# TAMDL_V2.net
KiCad netlist of a schematic drawn in EAGLE
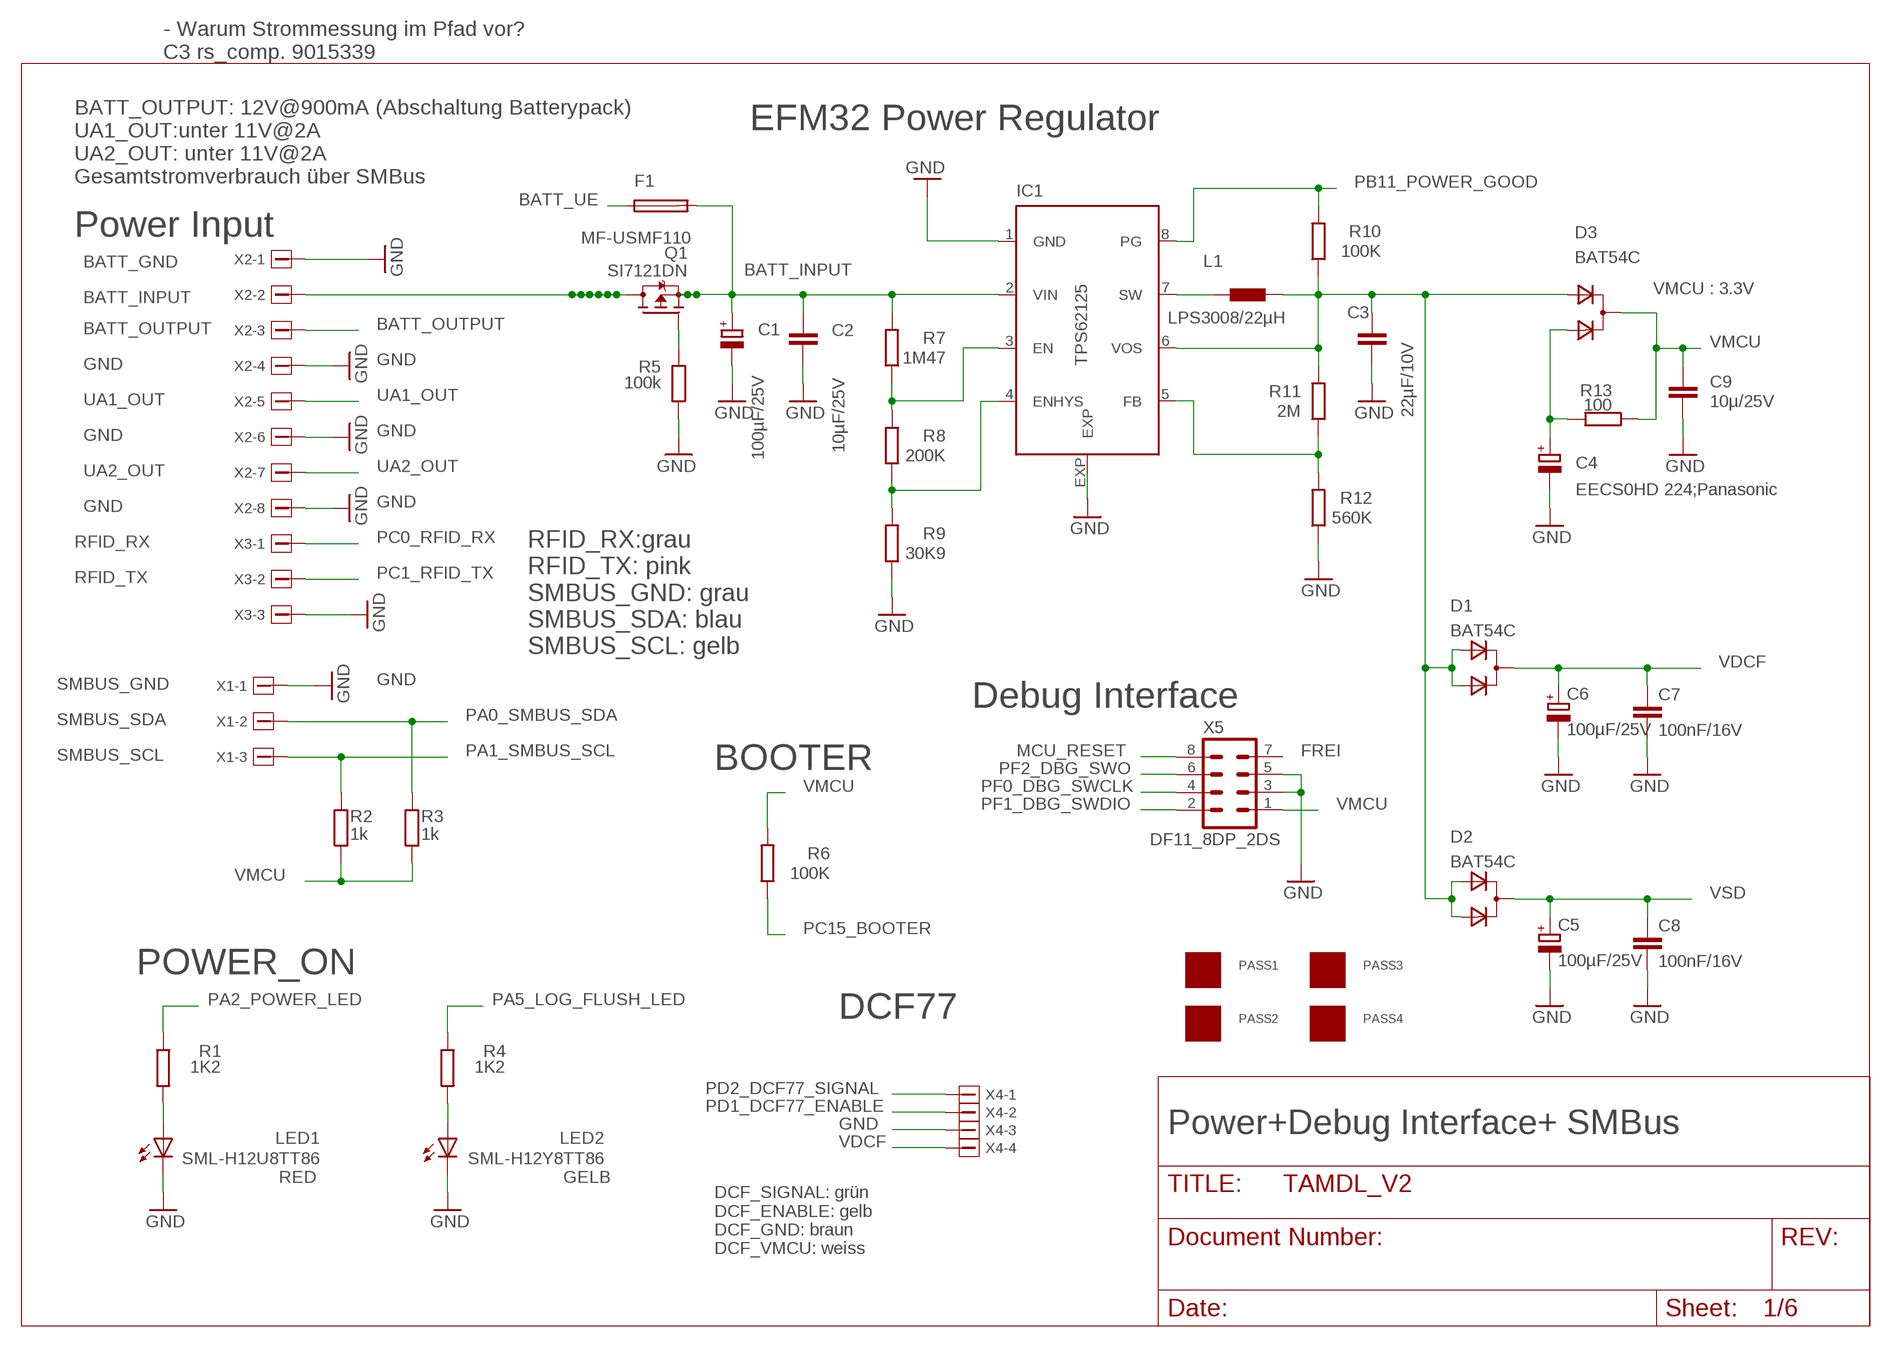
[diagram p0: schematic, sheet 1]
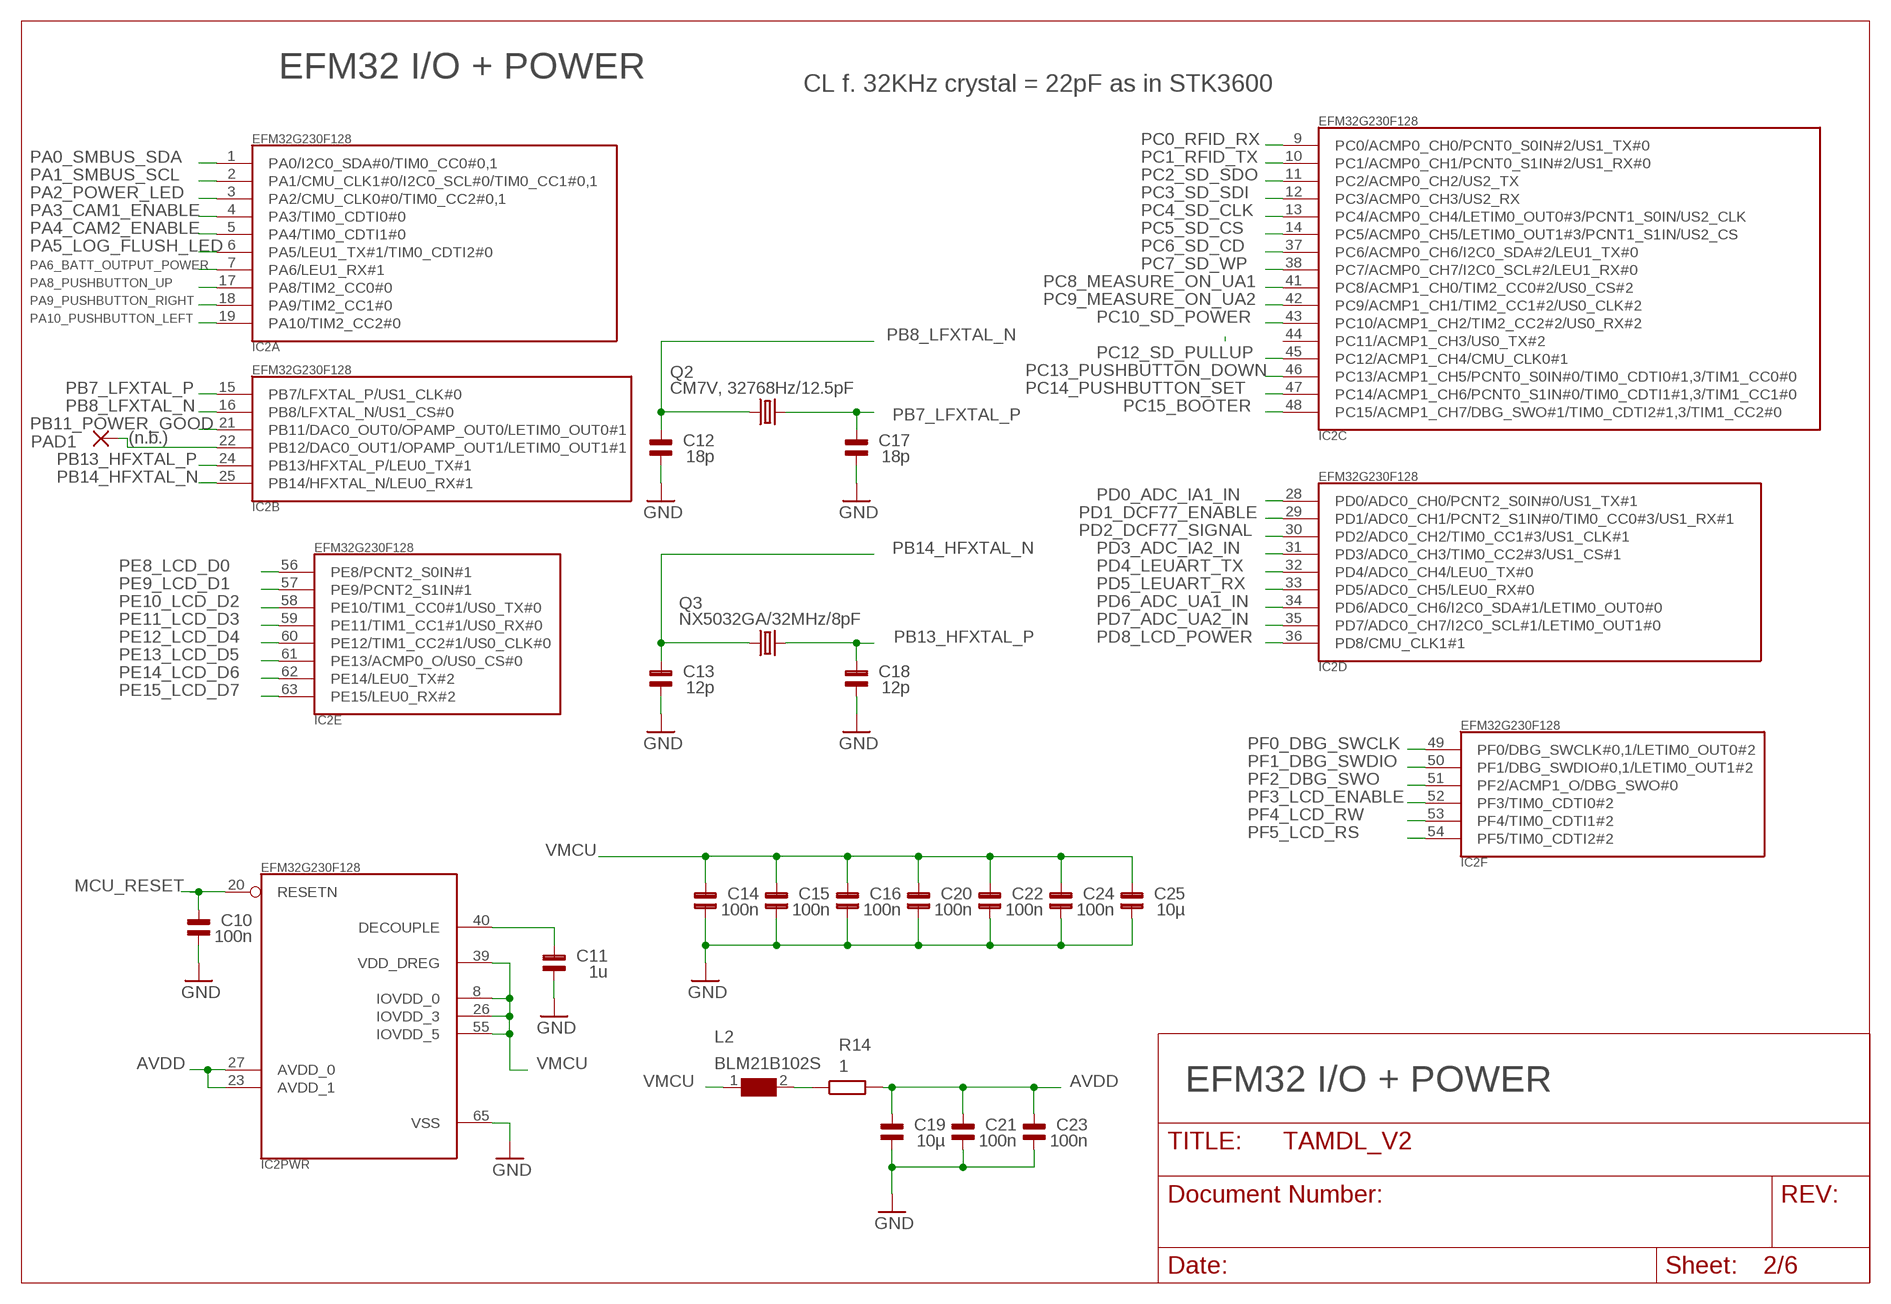
[diagram p1: schematic, sheet 2]
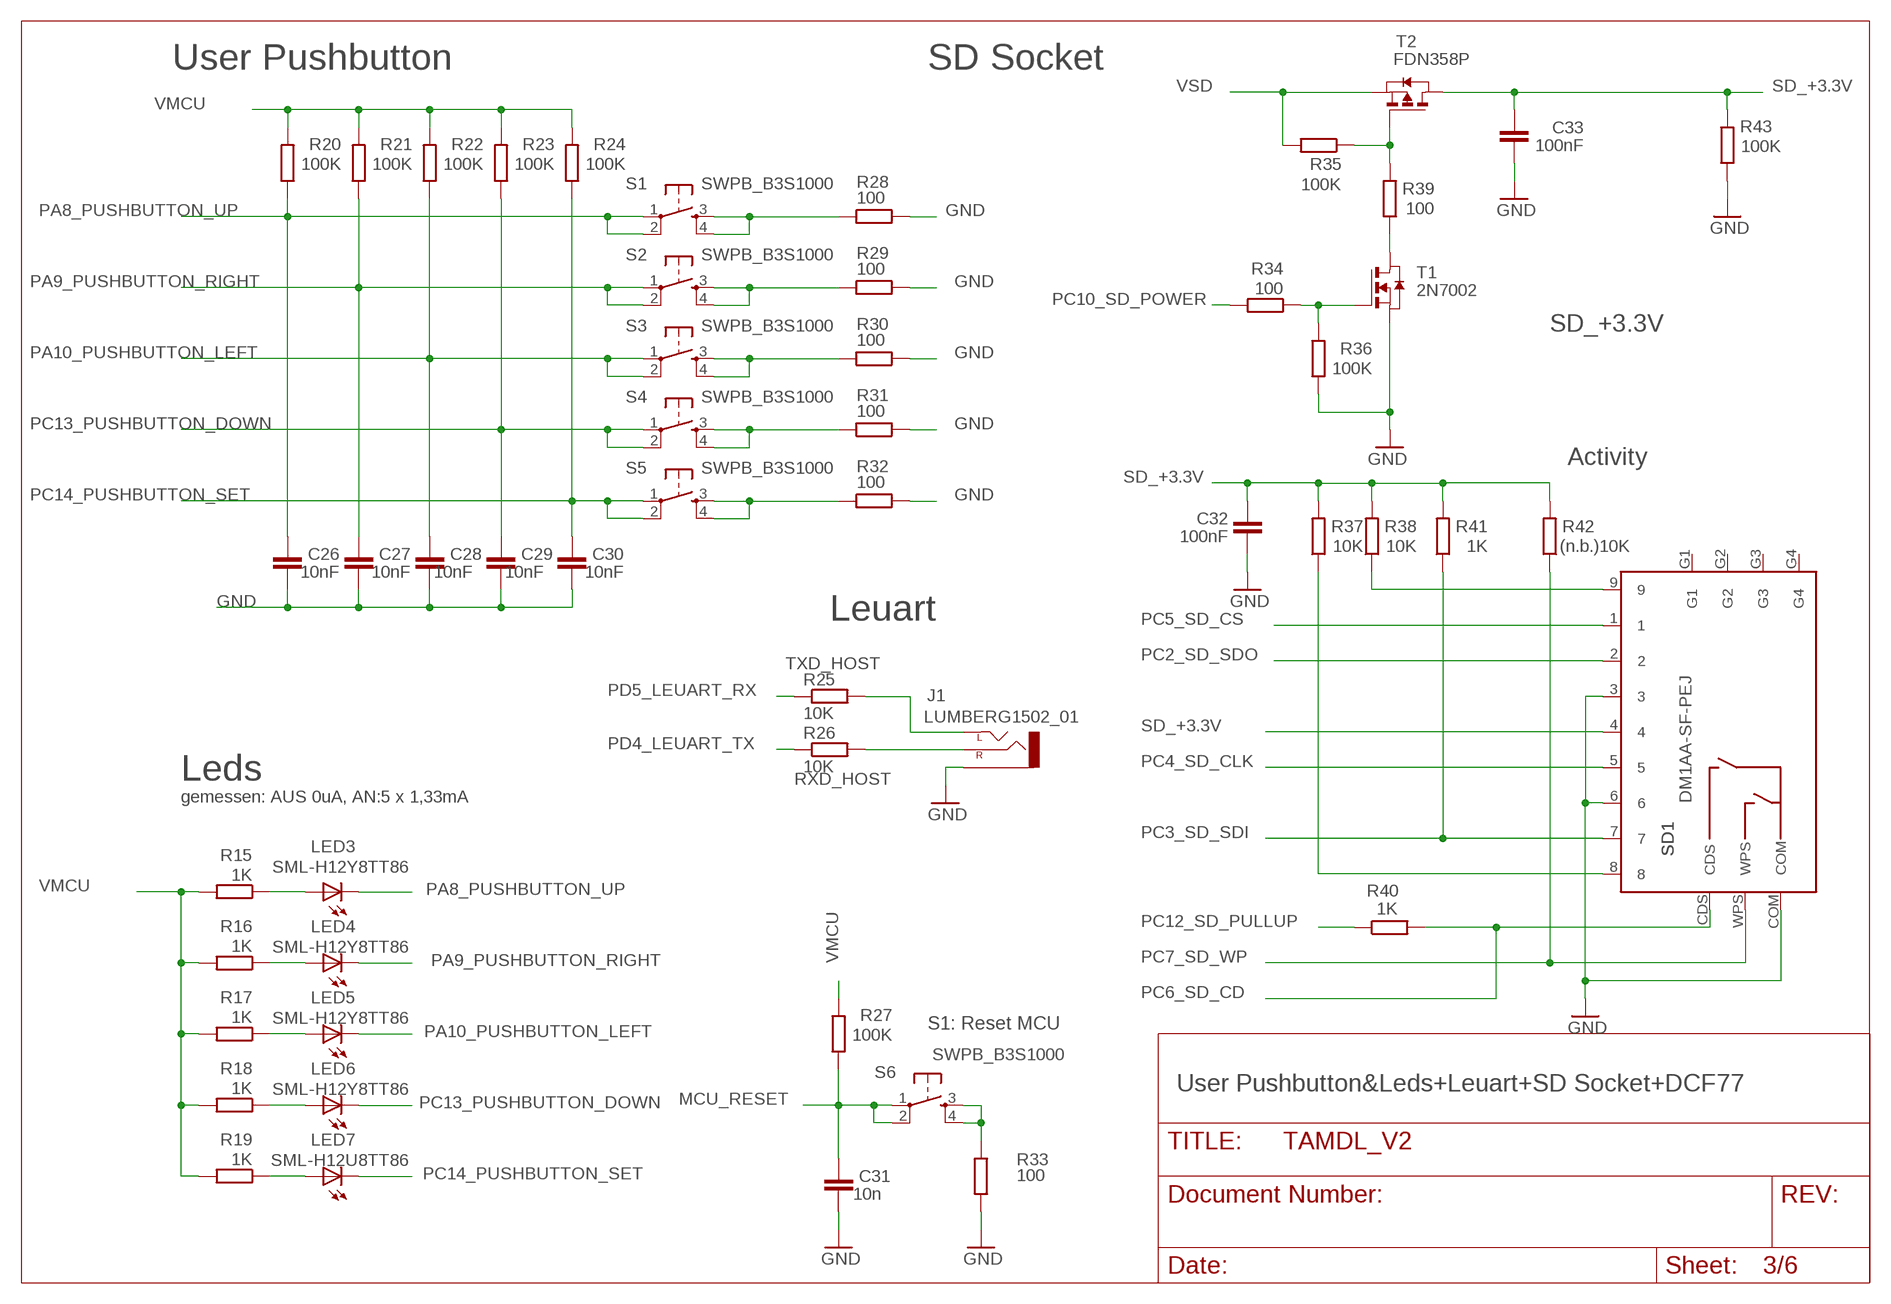
[diagram p2: schematic, sheet 3]
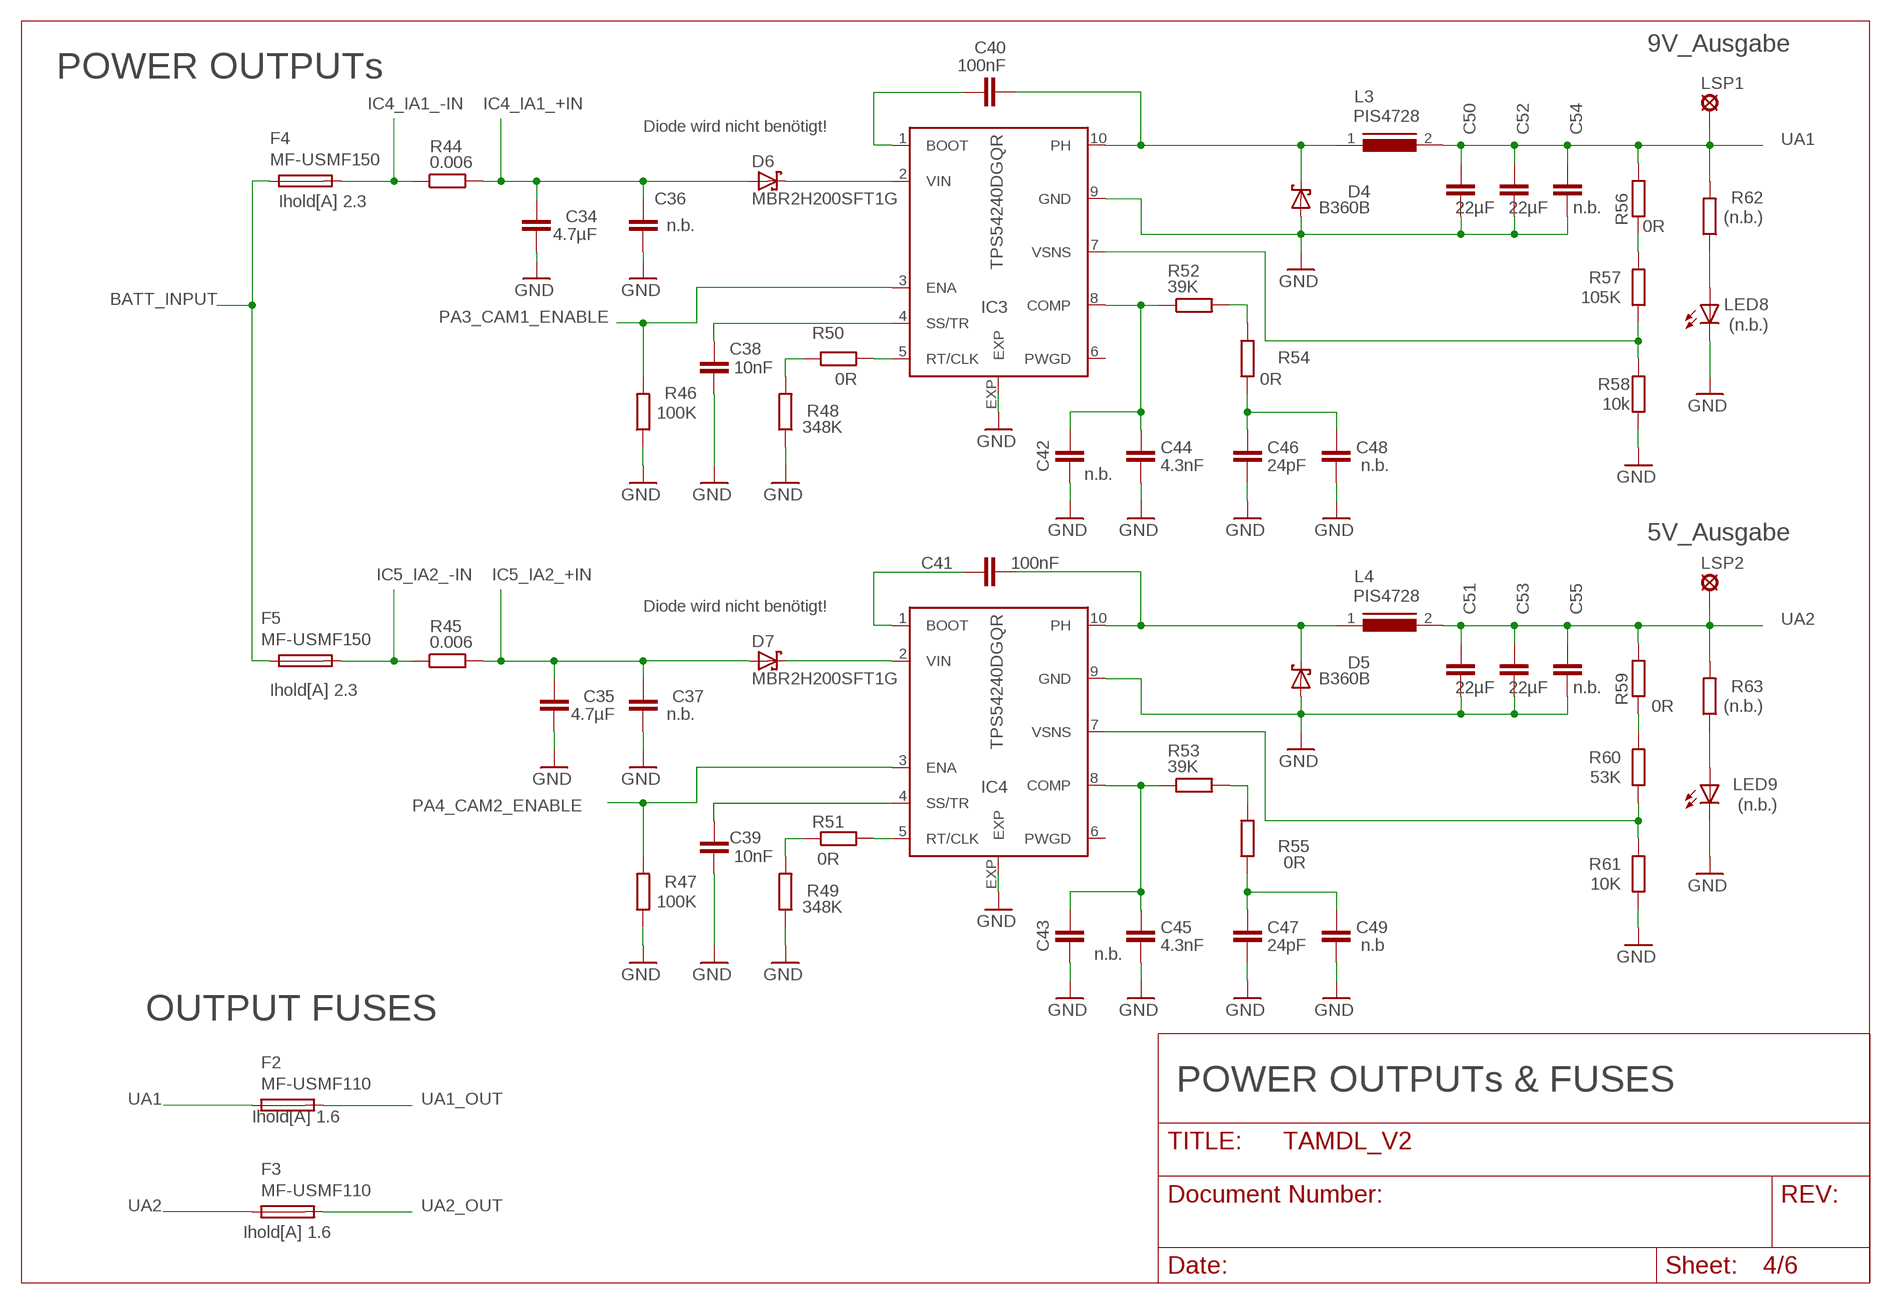
[diagram p3: schematic, sheet 4]
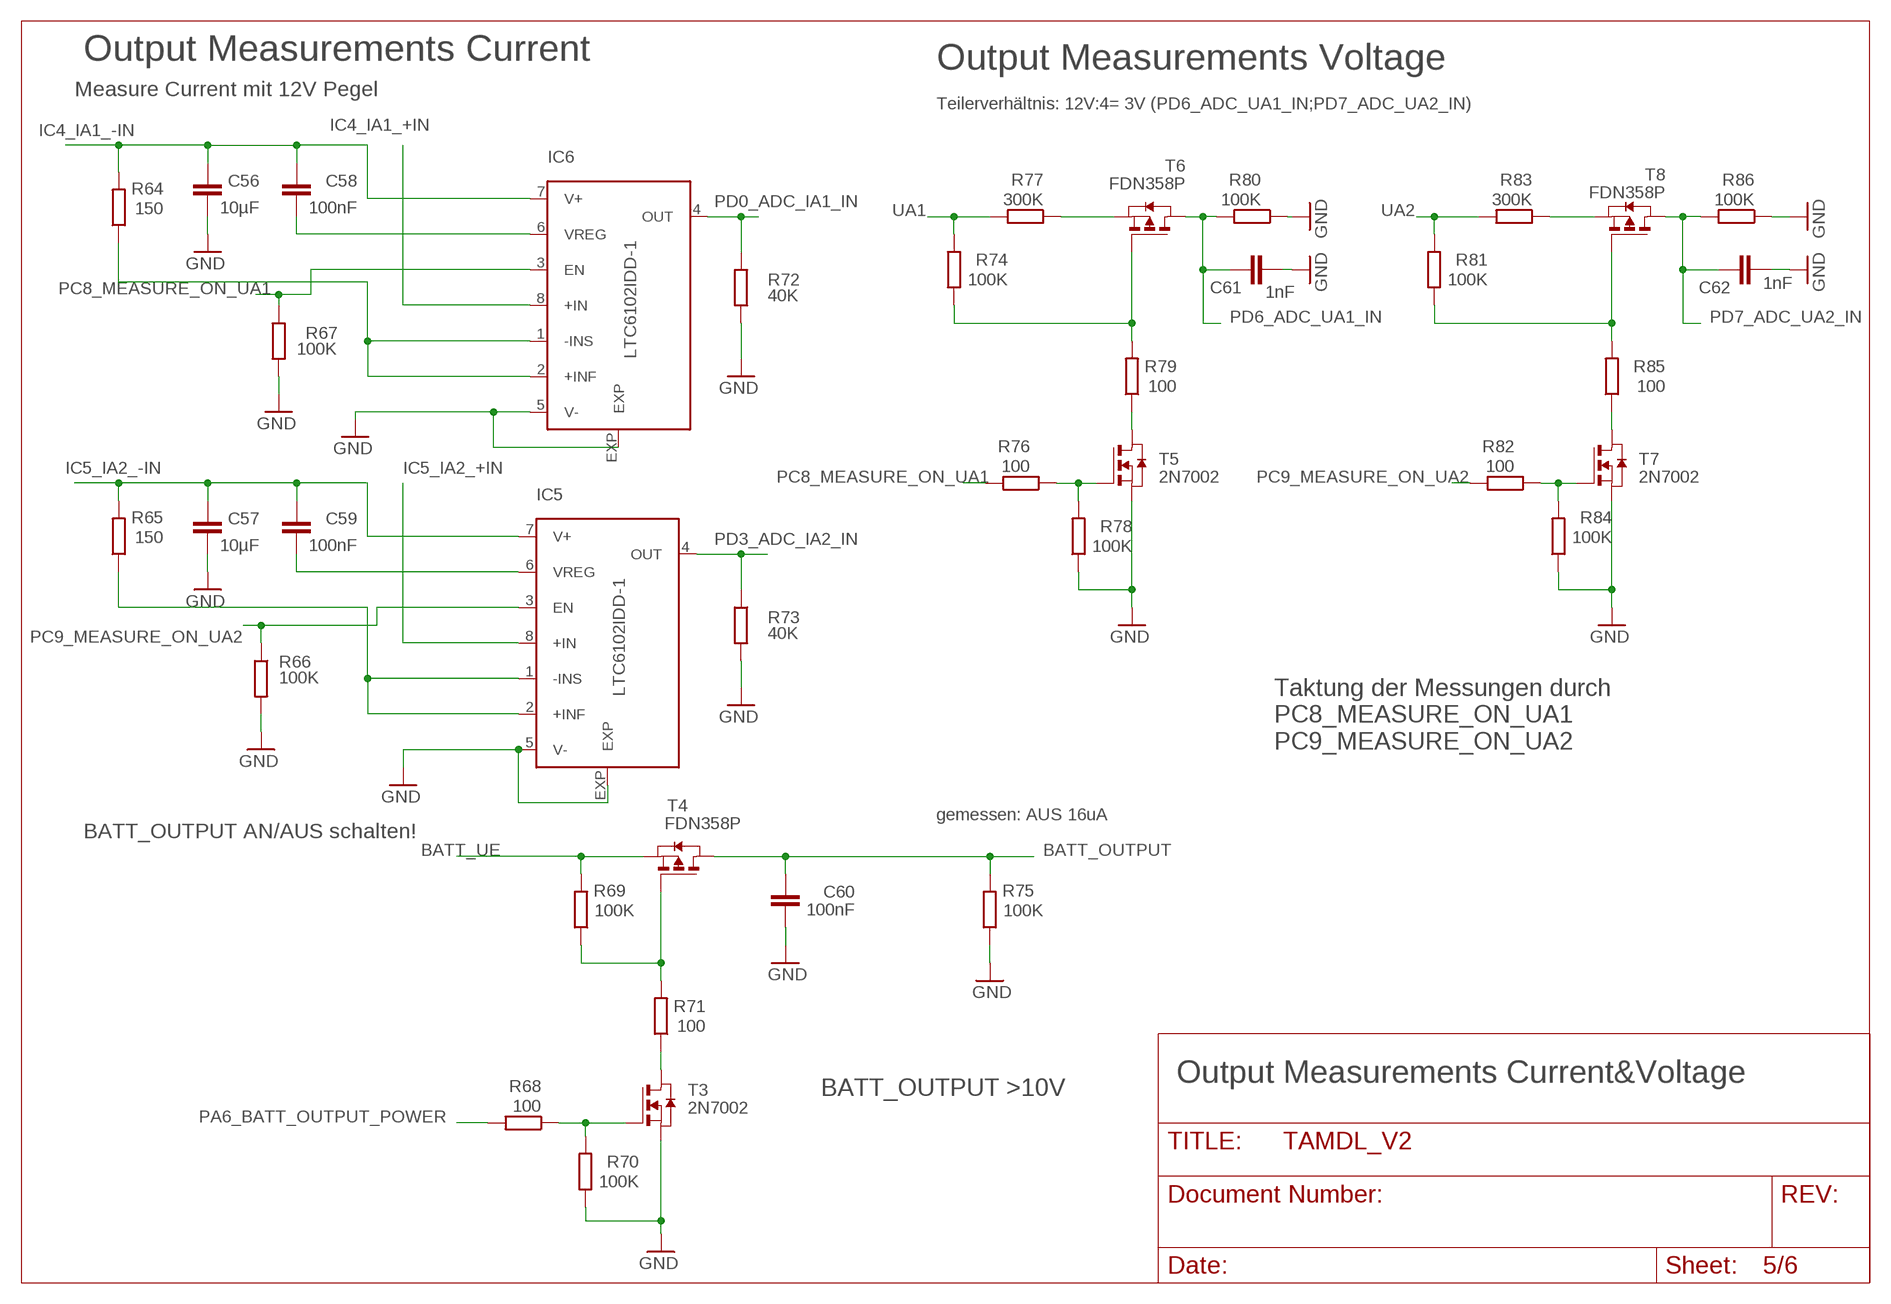
[diagram p4: schematic, sheet 5]
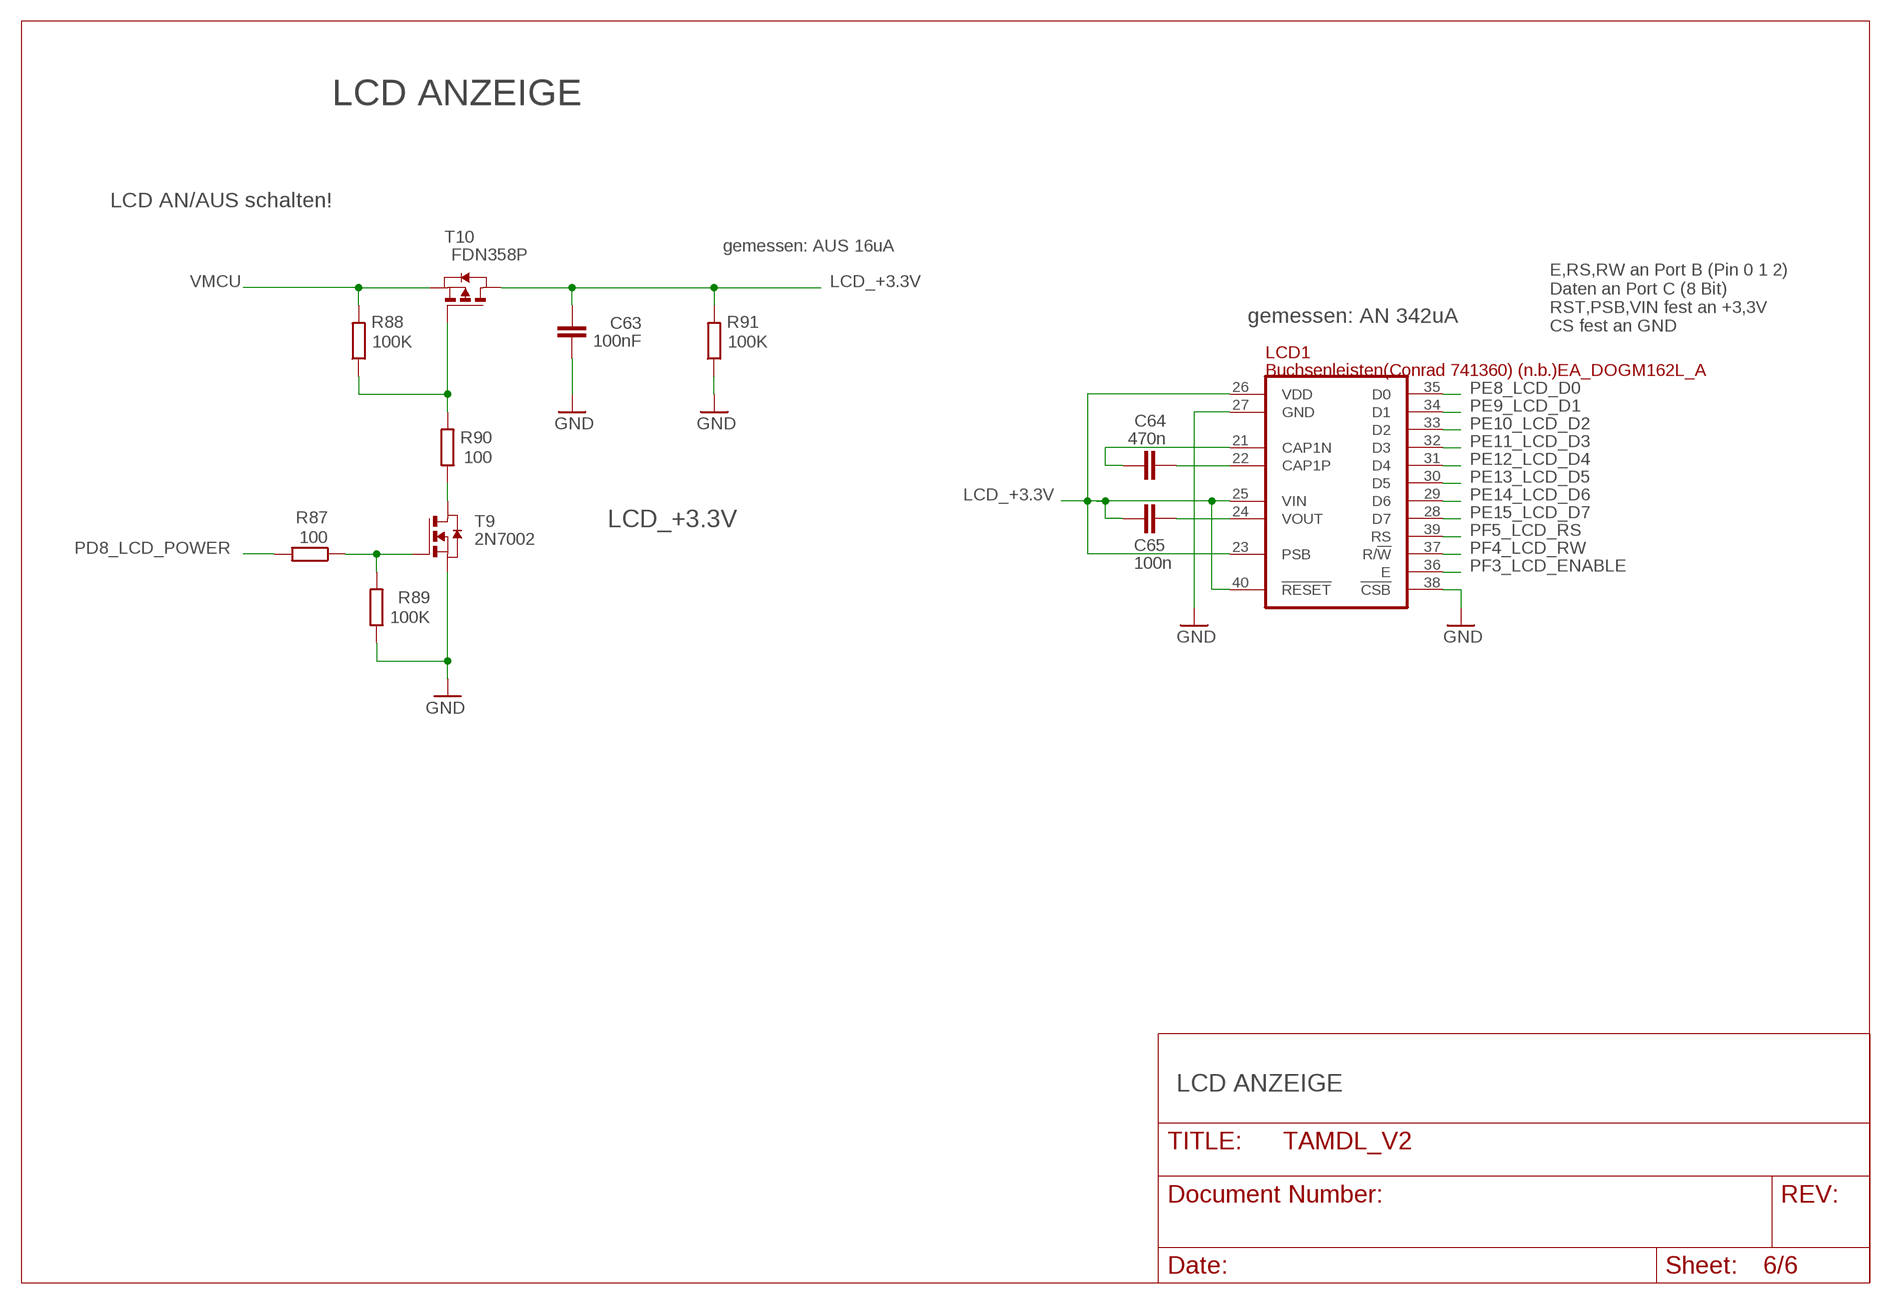
[diagram p5: schematic, sheet 6]

(export (version "E")
  (design (tool "Eeschema 10.0.6"))
  (components
    (comp (ref "C63")
      (value "100nF")
      (footprint "eagle-import:C0603")
      (libsource (lib "eagle-import") (part "resistor_C-EUC0603"))
    )
    (comp (ref "C64")
      (value "470n")
      (footprint "eagle-import:C0805")
      (libsource (lib "eagle-import") (part "C-EUC0805"))
    )
    (comp (ref "C65")
      (value "100n")
      (footprint "eagle-import:C1206")
      (libsource (lib "eagle-import") (part "C-EUC1206"))
    )
    (comp (ref "LCD1")
      (value "Buchsenleisten(Conrad 741360) (n.b.)EA_DOGM162L_A")
      (footprint "eagle-import:EA_DOGM")
      (libsource (lib "eagle-import") (part "EA_DOGM162"))
    )
    (comp (ref "R87")
      (value "100")
      (footprint "eagle-import:R0805")
      (libsource (lib "eagle-import") (part "resistor_R-EU_R0805"))
    )
    (comp (ref "R88")
      (value "100K")
      (footprint "eagle-import:R0805")
      (libsource (lib "eagle-import") (part "resistor_R-EU_R0805"))
    )
    (comp (ref "R89")
      (value "100K")
      (footprint "eagle-import:R0805")
      (libsource (lib "eagle-import") (part "resistor_R-EU_R0805"))
    )
    (comp (ref "R90")
      (value "100")
      (footprint "eagle-import:R0805")
      (libsource (lib "eagle-import") (part "resistor_R-EU_R0805"))
    )
    (comp (ref "R91")
      (value "100K")
      (footprint "eagle-import:R0805")
      (libsource (lib "eagle-import") (part "resistor_R-EU_R0805"))
    )
    (comp (ref "T9")
      (value "2N7002")
      (footprint "eagle-import:ZETEX_SOT-23")
      (libsource (lib "eagle-import") (part "ZETEX_NMOSSOT23"))
    )
    (comp (ref "T10")
      (value "FDN358P")
      (footprint "eagle-import:ZETEX_SOT-23")
      (libsource (lib "eagle-import") (part "ZETEX_PMOSSOT23"))
    )
    (comp (ref "C26")
      (value "10nF")
      (footprint "eagle-import:C0603")
      (libsource (lib "eagle-import") (part "resistor_C-EUC0603"))
    )
    (comp (ref "C27")
      (value "10nF")
      (footprint "eagle-import:C0603")
      (libsource (lib "eagle-import") (part "resistor_C-EUC0603"))
    )
    (comp (ref "C28")
      (value "10nF")
      (footprint "eagle-import:C0603")
      (libsource (lib "eagle-import") (part "resistor_C-EUC0603"))
    )
    (comp (ref "C29")
      (value "10nF")
      (footprint "eagle-import:C0603")
      (libsource (lib "eagle-import") (part "resistor_C-EUC0603"))
    )
    (comp (ref "C30")
      (value "10nF")
      (footprint "eagle-import:C0603")
      (libsource (lib "eagle-import") (part "resistor_C-EUC0603"))
    )
    (comp (ref "C31")
      (value "10n")
      (footprint "eagle-import:C0603")
      (libsource (lib "eagle-import") (part "resistor_C-EUC0603"))
    )
    (comp (ref "C32")
      (value "100nF")
      (footprint "eagle-import:C0603")
      (libsource (lib "eagle-import") (part "resistor_C-EUC0603"))
    )
    (comp (ref "C33")
      (value "100nF")
      (footprint "eagle-import:C0603")
      (libsource (lib "eagle-import") (part "resistor_C-EUC0603"))
    )
    (comp (ref "J1")
      (value "LUMBERG1502_01")
      (footprint "eagle-import:LUMBERG1502_01")
      (libsource (lib "eagle-import") (part "LUMBERG1502_01"))
    )
    (comp (ref "LED3")
      (value "SML-H12Y8TT86")
      (footprint "eagle-import:CHIPLED_0805")
      (libsource (lib "eagle-import") (part "LEDCHIPLED_0805"))
    )
    (comp (ref "LED4")
      (value "SML-H12Y8TT86")
      (footprint "eagle-import:CHIPLED_0805")
      (libsource (lib "eagle-import") (part "LEDCHIPLED_0805"))
    )
    (comp (ref "LED5")
      (value "SML-H12Y8TT86")
      (footprint "eagle-import:CHIPLED_0805")
      (libsource (lib "eagle-import") (part "LEDCHIPLED_0805"))
    )
    (comp (ref "LED6")
      (value "SML-H12Y8TT86")
      (footprint "eagle-import:CHIPLED_0805")
      (libsource (lib "eagle-import") (part "LEDCHIPLED_0805"))
    )
    (comp (ref "LED7")
      (value "SML-H12U8TT86")
      (footprint "eagle-import:CHIPLED_0805")
      (libsource (lib "eagle-import") (part "LEDCHIPLED_0805"))
    )
    (comp (ref "R15")
      (value "1K")
      (footprint "eagle-import:R0805")
      (libsource (lib "eagle-import") (part "resistor_R-EU_R0805"))
    )
    (comp (ref "R16")
      (value "1K")
      (footprint "eagle-import:R0805")
      (libsource (lib "eagle-import") (part "resistor_R-EU_R0805"))
    )
    (comp (ref "R17")
      (value "1K")
      (footprint "eagle-import:R0805")
      (libsource (lib "eagle-import") (part "resistor_R-EU_R0805"))
    )
    (comp (ref "R18")
      (value "1K")
      (footprint "eagle-import:R0805")
      (libsource (lib "eagle-import") (part "resistor_R-EU_R0805"))
    )
    (comp (ref "R19")
      (value "1K")
      (footprint "eagle-import:R0805")
      (libsource (lib "eagle-import") (part "resistor_R-EU_R0805"))
    )
    (comp (ref "R20")
      (value "100K")
      (footprint "eagle-import:R0805")
      (libsource (lib "eagle-import") (part "resistor_R-EU_R0805"))
    )
    (comp (ref "R21")
      (value "100K")
      (footprint "eagle-import:R0805")
      (libsource (lib "eagle-import") (part "resistor_R-EU_R0805"))
    )
    (comp (ref "R22")
      (value "100K")
      (footprint "eagle-import:R0805")
      (libsource (lib "eagle-import") (part "resistor_R-EU_R0805"))
    )
    (comp (ref "R23")
      (value "100K")
      (footprint "eagle-import:R0805")
      (libsource (lib "eagle-import") (part "resistor_R-EU_R0805"))
    )
    (comp (ref "R24")
      (value "100K")
      (footprint "eagle-import:R0805")
      (libsource (lib "eagle-import") (part "resistor_R-EU_R0805"))
    )
    (comp (ref "R25")
      (value "10K")
      (footprint "eagle-import:R0805")
      (libsource (lib "eagle-import") (part "resistor_R-EU_R0805"))
    )
    (comp (ref "R26")
      (value "10K")
      (footprint "eagle-import:R0805")
      (libsource (lib "eagle-import") (part "resistor_R-EU_R0805"))
    )
    (comp (ref "R27")
      (value "100K")
      (footprint "eagle-import:R0805")
      (libsource (lib "eagle-import") (part "resistor_R-EU_R0805"))
    )
    (comp (ref "R28")
      (value "100")
      (footprint "eagle-import:R0805")
      (libsource (lib "eagle-import") (part "resistor_R-EU_R0805"))
    )
    (comp (ref "R29")
      (value "100")
      (footprint "eagle-import:R0805")
      (libsource (lib "eagle-import") (part "resistor_R-EU_R0805"))
    )
    (comp (ref "R30")
      (value "100")
      (footprint "eagle-import:R0805")
      (libsource (lib "eagle-import") (part "resistor_R-EU_R0805"))
    )
    (comp (ref "R31")
      (value "100")
      (footprint "eagle-import:R0805")
      (libsource (lib "eagle-import") (part "resistor_R-EU_R0805"))
    )
    (comp (ref "R32")
      (value "100")
      (footprint "eagle-import:R0805")
      (libsource (lib "eagle-import") (part "resistor_R-EU_R0805"))
    )
    (comp (ref "R33")
      (value "100")
      (footprint "eagle-import:R0805")
      (libsource (lib "eagle-import") (part "resistor_R-EU_R0805"))
    )
    (comp (ref "R34")
      (value "100")
      (footprint "eagle-import:R0805")
      (libsource (lib "eagle-import") (part "resistor_R-EU_R0805"))
    )
    (comp (ref "R35")
      (value "100K")
      (footprint "eagle-import:R0805")
      (libsource (lib "eagle-import") (part "resistor_R-EU_R0805"))
    )
    (comp (ref "R36")
      (value "100K")
      (footprint "eagle-import:R0805")
      (libsource (lib "eagle-import") (part "resistor_R-EU_R0805"))
    )
    (comp (ref "R37")
      (value "10K")
      (footprint "eagle-import:R0805")
      (libsource (lib "eagle-import") (part "resistor_R-EU_R0805"))
    )
    (comp (ref "R38")
      (value "10K")
      (footprint "eagle-import:R0805")
      (libsource (lib "eagle-import") (part "resistor_R-EU_R0805"))
    )
    (comp (ref "R39")
      (value "100")
      (footprint "eagle-import:R0805")
      (libsource (lib "eagle-import") (part "resistor_R-EU_R0805"))
    )
    (comp (ref "R40")
      (value "1K")
      (footprint "eagle-import:R0805")
      (libsource (lib "eagle-import") (part "resistor_R-EU_R0805"))
    )
    (comp (ref "R41")
      (value "1K")
      (footprint "eagle-import:R0805")
      (libsource (lib "eagle-import") (part "resistor_R-EU_R0805"))
    )
    (comp (ref "R42")
      (value "(n.b.)10K")
      (footprint "eagle-import:R0805")
      (libsource (lib "eagle-import") (part "resistor_R-EU_R0805"))
    )
    (comp (ref "R43")
      (value "100K")
      (footprint "eagle-import:R0805")
      (libsource (lib "eagle-import") (part "resistor_R-EU_R0805"))
    )
    (comp (ref "S1")
      (value "SWPB_B3S1000")
      (footprint "eagle-import:DTSM-6")
      (libsource (lib "eagle-import") (part "DTSM-6"))
    )
    (comp (ref "S2")
      (value "SWPB_B3S1000")
      (footprint "eagle-import:DTSM-6")
      (libsource (lib "eagle-import") (part "DTSM-6"))
    )
    (comp (ref "S3")
      (value "SWPB_B3S1000")
      (footprint "eagle-import:DTSM-6")
      (libsource (lib "eagle-import") (part "DTSM-6"))
    )
    (comp (ref "S4")
      (value "SWPB_B3S1000")
      (footprint "eagle-import:DTSM-6")
      (libsource (lib "eagle-import") (part "DTSM-6"))
    )
    (comp (ref "S5")
      (value "SWPB_B3S1000")
      (footprint "eagle-import:DTSM-6")
      (libsource (lib "eagle-import") (part "DTSM-6"))
    )
    (comp (ref "S6")
      (value "SWPB_B3S1000")
      (footprint "eagle-import:DTSM-6")
      (libsource (lib "eagle-import") (part "DTSM-6"))
    )
    (comp (ref "SD1")
      (value "DM1AA-SF-PEJ")
      (footprint "eagle-import:DM1AA-SF-PEJ")
      (libsource (lib "eagle-import") (part "DM1AA-SF-PEJ"))
    )
    (comp (ref "T1")
      (value "2N7002")
      (footprint "eagle-import:ZETEX_SOT-23")
      (libsource (lib "eagle-import") (part "ZETEX_NMOSSOT23"))
    )
    (comp (ref "T2")
      (value "FDN358P")
      (footprint "eagle-import:ZETEX_SOT-23")
      (libsource (lib "eagle-import") (part "ZETEX_PMOSSOT23"))
    )
    (comp (ref "C34")
      (value "4.7µF")
      (footprint "eagle-import:C1210")
      (libsource (lib "eagle-import") (part "C-EUC1210"))
    )
    (comp (ref "C35")
      (value "4.7µF")
      (footprint "eagle-import:C1210")
      (libsource (lib "eagle-import") (part "C-EUC1210"))
    )
    (comp (ref "C36")
      (value "n.b.")
      (footprint "eagle-import:C1210")
      (libsource (lib "eagle-import") (part "C-EUC1210"))
    )
    (comp (ref "C37")
      (value "n.b.")
      (footprint "eagle-import:C1210")
      (libsource (lib "eagle-import") (part "C-EUC1210"))
    )
    (comp (ref "C38")
      (value "10nF")
      (footprint "eagle-import:C0603")
      (libsource (lib "eagle-import") (part "C-EUC0603"))
    )
    (comp (ref "C39")
      (value "10nF")
      (footprint "eagle-import:C0603")
      (libsource (lib "eagle-import") (part "C-EUC0603"))
    )
    (comp (ref "C40")
      (value "100nF")
      (footprint "eagle-import:C0603")
      (libsource (lib "eagle-import") (part "C-EUC0603"))
    )
    (comp (ref "C41")
      (value "100nF")
      (footprint "eagle-import:C0603")
      (libsource (lib "eagle-import") (part "C-EUC0603"))
    )
    (comp (ref "C42")
      (value "n.b.")
      (footprint "eagle-import:C0603")
      (libsource (lib "eagle-import") (part "C-EUC0603"))
    )
    (comp (ref "C43")
      (value "n.b.")
      (footprint "eagle-import:C0603")
      (libsource (lib "eagle-import") (part "C-EUC0603"))
    )
    (comp (ref "C44")
      (value "4.3nF")
      (footprint "eagle-import:C0603")
      (libsource (lib "eagle-import") (part "C-EUC0603"))
    )
    (comp (ref "C45")
      (value "4.3nF")
      (footprint "eagle-import:C0603")
      (libsource (lib "eagle-import") (part "C-EUC0603"))
    )
    (comp (ref "C46")
      (value "24pF")
      (footprint "eagle-import:C0603")
      (libsource (lib "eagle-import") (part "C-EUC0603"))
    )
    (comp (ref "C47")
      (value "24pF")
      (footprint "eagle-import:C0603")
      (libsource (lib "eagle-import") (part "C-EUC0603"))
    )
    (comp (ref "C48")
      (value "n.b.")
      (footprint "eagle-import:C0603")
      (libsource (lib "eagle-import") (part "C-EUC0603"))
    )
    (comp (ref "C49")
      (value "n.b")
      (footprint "eagle-import:C0603")
      (libsource (lib "eagle-import") (part "C-EUC0603"))
    )
    (comp (ref "C50")
      (value "22µF")
      (footprint "eagle-import:C1210")
      (libsource (lib "eagle-import") (part "C-EUC1210"))
    )
    (comp (ref "C51")
      (value "22µF")
      (footprint "eagle-import:C1210")
      (libsource (lib "eagle-import") (part "C-EUC1210"))
    )
    (comp (ref "C52")
      (value "22µF")
      (footprint "eagle-import:C1210")
      (libsource (lib "eagle-import") (part "C-EUC1210"))
    )
    (comp (ref "C53")
      (value "22µF")
      (footprint "eagle-import:C1210")
      (libsource (lib "eagle-import") (part "C-EUC1210"))
    )
    (comp (ref "C54")
      (value "n.b.")
      (footprint "eagle-import:C1210")
      (libsource (lib "eagle-import") (part "C-EUC1210"))
    )
    (comp (ref "C55")
      (value "n.b.")
      (footprint "eagle-import:C1210")
      (libsource (lib "eagle-import") (part "C-EUC1210"))
    )
    (comp (ref "D4")
      (value "B360B")
      (footprint "eagle-import:SMB")
      (libsource (lib "eagle-import") (part "SCHOTTKY-DIODESMD"))
    )
    (comp (ref "D5")
      (value "B360B")
      (footprint "eagle-import:SMB")
      (libsource (lib "eagle-import") (part "SCHOTTKY-DIODESMD"))
    )
    (comp (ref "D6")
      (value "MBR2H200SFT1G")
      (footprint "eagle-import:SOD123FL")
      (libsource (lib "eagle-import") (part "SMF5.0AT1"))
    )
    (comp (ref "D7")
      (value "MBR2H200SFT1G")
      (footprint "eagle-import:SOD123FL")
      (libsource (lib "eagle-import") (part "SMF5.0AT1"))
    )
    (comp (ref "F2")
      (value "MF-USMF110")
      (footprint "eagle-import:PFUF_1210POLY")
      (libsource (lib "eagle-import") (part "PFUF"))
    )
    (comp (ref "F3")
      (value "MF-USMF110")
      (footprint "eagle-import:PFUF_1210POLY")
      (libsource (lib "eagle-import") (part "PFUF"))
    )
    (comp (ref "F4")
      (value "MF-USMF150")
      (footprint "eagle-import:PFUF_1210POLY")
      (libsource (lib "eagle-import") (part "PFUF"))
    )
    (comp (ref "F5")
      (value "MF-USMF150")
      (footprint "eagle-import:PFUF_1210POLY")
      (libsource (lib "eagle-import") (part "PFUF"))
    )
    (comp (ref "IC3")
      (value "TPS54240DGQR")
      (footprint "eagle-import:S-PDSO-G10")
      (libsource (lib "eagle-import") (part "TPS54240DGQR"))
    )
    (comp (ref "IC4")
      (value "TPS54240DGQR")
      (footprint "eagle-import:S-PDSO-G10")
      (libsource (lib "eagle-import") (part "TPS54240DGQR"))
    )
    (comp (ref "L3")
      (value "PIS4728")
      (footprint "eagle-import:DR127")
      (libsource (lib "eagle-import") (part "DR127"))
    )
    (comp (ref "L4")
      (value "PIS4728")
      (footprint "eagle-import:DR127")
      (libsource (lib "eagle-import") (part "DR127"))
    )
    (comp (ref "LED8")
      (value "(n.b.)")
      (footprint "eagle-import:CHIPLED_0805")
      (libsource (lib "eagle-import") (part "LEDCHIPLED_0805"))
    )
    (comp (ref "LED9")
      (value "(n.b.)")
      (footprint "eagle-import:CHIPLED_0805")
      (libsource (lib "eagle-import") (part "LEDCHIPLED_0805"))
    )
    (comp (ref "LSP1")
      (value "(n.b.)SE13")
      (footprint "eagle-import:SE13")
      (libsource (lib "eagle-import") (part "SE13"))
    )
    (comp (ref "LSP2")
      (value "(n.b.)SE13")
      (footprint "eagle-import:SE13")
      (libsource (lib "eagle-import") (part "SE13"))
    )
    (comp (ref "R44")
      (value "0.006")
      (footprint "eagle-import:R2512W")
      (libsource (lib "eagle-import") (part "R-EU_R2512W"))
    )
    (comp (ref "R45")
      (value "0.006")
      (footprint "eagle-import:R2512W")
      (libsource (lib "eagle-import") (part "R-EU_R2512W"))
    )
    (comp (ref "R46")
      (value "100K")
      (footprint "eagle-import:R0805")
      (libsource (lib "eagle-import") (part "resistor_R-EU_R0805"))
    )
    (comp (ref "R47")
      (value "100K")
      (footprint "eagle-import:R0805")
      (libsource (lib "eagle-import") (part "resistor_R-EU_R0805"))
    )
    (comp (ref "R48")
      (value "348K")
      (footprint "eagle-import:R0805")
      (libsource (lib "eagle-import") (part "resistor_R-EU_R0805"))
    )
    (comp (ref "R49")
      (value "348K")
      (footprint "eagle-import:R0805")
      (libsource (lib "eagle-import") (part "resistor_R-EU_R0805"))
    )
    (comp (ref "R50")
      (value "0R")
      (footprint "eagle-import:R0805")
      (libsource (lib "eagle-import") (part "resistor_R-EU_R0805"))
    )
    (comp (ref "R51")
      (value "0R")
      (footprint "eagle-import:R0805")
      (libsource (lib "eagle-import") (part "resistor_R-EU_R0805"))
    )
    (comp (ref "R52")
      (value "39K")
      (footprint "eagle-import:R0805")
      (libsource (lib "eagle-import") (part "resistor_R-EU_R0805"))
    )
    (comp (ref "R53")
      (value "39K")
      (footprint "eagle-import:R0805")
      (libsource (lib "eagle-import") (part "resistor_R-EU_R0805"))
    )
    (comp (ref "R54")
      (value "0R")
      (footprint "eagle-import:R0805")
      (libsource (lib "eagle-import") (part "resistor_R-EU_R0805"))
    )
    (comp (ref "R55")
      (value "0R")
      (footprint "eagle-import:R0805")
      (libsource (lib "eagle-import") (part "resistor_R-EU_R0805"))
    )
    (comp (ref "R56")
      (value "0R")
      (footprint "eagle-import:R0805")
      (libsource (lib "eagle-import") (part "resistor_R-EU_R0805"))
    )
    (comp (ref "R57")
      (value "105K")
      (footprint "eagle-import:R0805")
      (libsource (lib "eagle-import") (part "resistor_R-EU_R0805"))
    )
    (comp (ref "R58")
      (value "10k")
      (footprint "eagle-import:R0805")
      (libsource (lib "eagle-import") (part "resistor_R-EU_R0805"))
    )
    (comp (ref "R59")
      (value "0R")
      (footprint "eagle-import:R0805")
      (libsource (lib "eagle-import") (part "resistor_R-EU_R0805"))
    )
    (comp (ref "R60")
      (value "53K")
      (footprint "eagle-import:R0805")
      (libsource (lib "eagle-import") (part "resistor_R-EU_R0805"))
    )
    (comp (ref "R61")
      (value "10K")
      (footprint "eagle-import:R0805")
      (libsource (lib "eagle-import") (part "resistor_R-EU_R0805"))
    )
    (comp (ref "R62")
      (value "(n.b.)")
      (footprint "eagle-import:R0805")
      (libsource (lib "eagle-import") (part "resistor_R-EU_R0805"))
    )
    (comp (ref "R63")
      (value "(n.b.)")
      (footprint "eagle-import:R0805")
      (libsource (lib "eagle-import") (part "resistor_R-EU_R0805"))
    )
    (comp (ref "C1")
      (value "100µF/25V")
      (footprint "eagle-import:PANASONIC_E")
      (libsource (lib "eagle-import") (part "CPOL-EUE"))
    )
    (comp (ref "C2")
      (value "10µF/25V")
      (footprint "eagle-import:C1206")
      (libsource (lib "eagle-import") (part "C-EUC1206"))
    )
    (comp (ref "C3")
      (value "22µF/10V")
      (footprint "eagle-import:C0603")
      (libsource (lib "eagle-import") (part "C-EUC0603"))
    )
    (comp (ref "C4")
      (value "EECS0HD 224;Panasonic")
      (footprint "eagle-import:GOLDCAPSPK-V")
      (libsource (lib "eagle-import") (part "GOLDCAPSPK-V"))
    )
    (comp (ref "C5")
      (value "100µF/25V")
      (footprint "eagle-import:PANASONIC_E")
      (libsource (lib "eagle-import") (part "CPOL-EUE"))
    )
    (comp (ref "C6")
      (value "100µF/25V")
      (footprint "eagle-import:PANASONIC_E")
      (libsource (lib "eagle-import") (part "CPOL-EUE"))
    )
    (comp (ref "C7")
      (value "100nF/16V")
      (footprint "eagle-import:C0805")
      (libsource (lib "eagle-import") (part "C-EUC0805"))
    )
    (comp (ref "C8")
      (value "100nF/16V")
      (footprint "eagle-import:C0805")
      (libsource (lib "eagle-import") (part "C-EUC0805"))
    )
    (comp (ref "C9")
      (value "10µ/25V")
      (footprint "eagle-import:C1206")
      (libsource (lib "eagle-import") (part "C-EUC1206"))
    )
    (comp (ref "D1")
      (value "BAT54C")
      (footprint "eagle-import:SOT-23$1")
      (libsource (lib "eagle-import") (part "D2A_SOT23"))
    )
    (comp (ref "D2")
      (value "BAT54C")
      (footprint "eagle-import:SOT-23$1")
      (libsource (lib "eagle-import") (part "D2A_SOT23"))
    )
    (comp (ref "D3")
      (value "BAT54C")
      (footprint "eagle-import:SOT-23$1")
      (libsource (lib "eagle-import") (part "D2A_SOT23"))
    )
    (comp (ref "F1")
      (value "MF-USMF110")
      (footprint "eagle-import:PFUF_1210POLY")
      (libsource (lib "eagle-import") (part "PFUF"))
    )
    (comp (ref "IC1")
      (value "TPS62125")
      (footprint "eagle-import:DSG_PWSO-N8_EXP")
      (libsource (lib "eagle-import") (part "TPS62125"))
    )
    (comp (ref "L1")
      (value "LPS3008/22µH")
      (footprint "eagle-import:LPS3008")
      (libsource (lib "eagle-import") (part "LPS3008"))
    )
    (comp (ref "LED1")
      (value "SML-H12U8TT86")
      (footprint "eagle-import:CHIPLED_0805")
      (libsource (lib "eagle-import") (part "LEDCHIPLED_0805"))
    )
    (comp (ref "LED2")
      (value "SML-H12Y8TT86")
      (footprint "eagle-import:CHIPLED_0805")
      (libsource (lib "eagle-import") (part "LEDCHIPLED_0805"))
    )
    (comp (ref "PASS1")
      (value "ROUND_1MM1.5")
      (footprint "eagle-import:ROUND2_1.5MM")
      (libsource (lib "eagle-import") (part "ROUND_1MM1.5"))
    )
    (comp (ref "PASS2")
      (value "ROUND_1MM1.5")
      (footprint "eagle-import:ROUND2_1.5MM")
      (libsource (lib "eagle-import") (part "ROUND_1MM1.5"))
    )
    (comp (ref "PASS3")
      (value "ROUND_1MM1.5")
      (footprint "eagle-import:ROUND2_1.5MM")
      (libsource (lib "eagle-import") (part "ROUND_1MM1.5"))
    )
    (comp (ref "PASS4")
      (value "ROUND_1MM1.5")
      (footprint "eagle-import:ROUND2_1.5MM")
      (libsource (lib "eagle-import") (part "ROUND_1MM1.5"))
    )
    (comp (ref "Q1")
      (value "SI7121DN")
      (footprint "eagle-import:TRANSISTOR-FET_1212-8S")
      (libsource (lib "eagle-import") (part "TRANSISTOR-FET_SI7113DN"))
    )
    (comp (ref "R1")
      (value "1K2")
      (footprint "eagle-import:R0805")
      (libsource (lib "eagle-import") (part "resistor_R-EU_R0805"))
    )
    (comp (ref "R2")
      (value "1k")
      (footprint "eagle-import:R0805")
      (libsource (lib "eagle-import") (part "resistor_R-EU_R0805"))
    )
    (comp (ref "R3")
      (value "1k")
      (footprint "eagle-import:R0805")
      (libsource (lib "eagle-import") (part "resistor_R-EU_R0805"))
    )
    (comp (ref "R4")
      (value "1K2")
      (footprint "eagle-import:R0805")
      (libsource (lib "eagle-import") (part "resistor_R-EU_R0805"))
    )
    (comp (ref "R5")
      (value "100k")
      (footprint "eagle-import:R0805")
      (libsource (lib "eagle-import") (part "resistor_R-EU_R0805"))
    )
    (comp (ref "R6")
      (value "100K")
      (footprint "eagle-import:R0805")
      (libsource (lib "eagle-import") (part "R-EU_R0805"))
    )
    (comp (ref "R7")
      (value "1M47")
      (footprint "eagle-import:R0805")
      (libsource (lib "eagle-import") (part "R-EU_R0805"))
    )
    (comp (ref "R8")
      (value "200K")
      (footprint "eagle-import:R0805")
      (libsource (lib "eagle-import") (part "R-EU_R0805"))
    )
    (comp (ref "R9")
      (value "30K9")
      (footprint "eagle-import:R0805")
      (libsource (lib "eagle-import") (part "R-EU_R0805"))
    )
    (comp (ref "R10")
      (value "100K")
      (footprint "eagle-import:R0805")
      (libsource (lib "eagle-import") (part "R-EU_R0805"))
    )
    (comp (ref "R11")
      (value "2M")
      (footprint "eagle-import:R0805")
      (libsource (lib "eagle-import") (part "R-EU_R0805"))
    )
    (comp (ref "R12")
      (value "560K")
      (footprint "eagle-import:R0805")
      (libsource (lib "eagle-import") (part "R-EU_R0805"))
    )
    (comp (ref "R13")
      (value "100")
      (footprint "eagle-import:R0805")
      (libsource (lib "eagle-import") (part "R-EU_R0805"))
    )
    (comp (ref "X1")
      (value "1803439")
      (footprint "eagle-import:1803439")
      (libsource (lib "eagle-import") (part "1803439"))
    )
    (comp (ref "X2")
      (value "1803484")
      (footprint "eagle-import:1803484")
      (libsource (lib "eagle-import") (part "1803484"))
    )
    (comp (ref "X3")
      (value "1803439")
      (footprint "eagle-import:1803439")
      (libsource (lib "eagle-import") (part "1803439"))
    )
    (comp (ref "X4")
      (value "1803442")
      (footprint "eagle-import:1803442")
      (libsource (lib "eagle-import") (part "1803442"))
    )
    (comp (ref "X5")
      (value "DF11_8DP_2DS")
      (footprint "eagle-import:DP11_8DP-2DS")
      (libsource (lib "eagle-import") (part "DP11_8DP_2DS"))
    )
    (comp (ref "C10")
      (value "100n")
      (footprint "eagle-import:0805")
      (libsource (lib "eagle-import") (part "C_SMD0805"))
    )
    (comp (ref "C11")
      (value "1u")
      (footprint "eagle-import:0805")
      (libsource (lib "eagle-import") (part "C_SMD0805"))
    )
    (comp (ref "C12")
      (value "18p")
      (footprint "eagle-import:0805")
      (libsource (lib "eagle-import") (part "C_SMD0805"))
    )
    (comp (ref "C13")
      (value "12p")
      (footprint "eagle-import:0805")
      (libsource (lib "eagle-import") (part "C_SMD0805"))
    )
    (comp (ref "C14")
      (value "100n")
      (footprint "eagle-import:0805")
      (libsource (lib "eagle-import") (part "C_SMD0805"))
    )
    (comp (ref "C15")
      (value "100n")
      (footprint "eagle-import:0805")
      (libsource (lib "eagle-import") (part "C_SMD0805"))
    )
    (comp (ref "C16")
      (value "100n")
      (footprint "eagle-import:0805")
      (libsource (lib "eagle-import") (part "C_SMD0805"))
    )
    (comp (ref "C17")
      (value "18p")
      (footprint "eagle-import:0805")
      (libsource (lib "eagle-import") (part "C_SMD0805"))
    )
    (comp (ref "C18")
      (value "12p")
      (footprint "eagle-import:0805")
      (libsource (lib "eagle-import") (part "C_SMD0805"))
    )
    (comp (ref "C19")
      (value "10µ")
      (footprint "eagle-import:0805")
      (libsource (lib "eagle-import") (part "C_SMD0805"))
    )
    (comp (ref "C20")
      (value "100n")
      (footprint "eagle-import:0805")
      (libsource (lib "eagle-import") (part "C_SMD0805"))
    )
    (comp (ref "C21")
      (value "100n")
      (footprint "eagle-import:0805")
      (libsource (lib "eagle-import") (part "C_SMD0805"))
    )
    (comp (ref "C22")
      (value "100n")
      (footprint "eagle-import:0805")
      (libsource (lib "eagle-import") (part "C_SMD0805"))
    )
    (comp (ref "C23")
      (value "100n")
      (footprint "eagle-import:0805")
      (libsource (lib "eagle-import") (part "C_SMD0805"))
    )
    (comp (ref "C24")
      (value "100n")
      (footprint "eagle-import:0805")
      (libsource (lib "eagle-import") (part "C_SMD0805"))
    )
    (comp (ref "C25")
      (value "10µ")
      (footprint "eagle-import:0805")
      (libsource (lib "eagle-import") (part "C_SMD0805"))
    )
    (comp (ref "IC2")
      (value "EFM32G230F128")
      (footprint "eagle-import:QFN64")
      (libsource (lib "eagle-import") (part "EFM32G230F128"))
    )
    (comp (ref "L2")
      (value "BLM21B102S")
      (footprint "eagle-import:0805")
      (fields (field (name "MPN") "7427920"))
      (libsource (lib "eagle-import") (part "WE-CBF_0805-7427920"))
    )
    (comp (ref "PAD1")
      (value "(n.b.)")
      (footprint "eagle-import:SMD1,27-2,54")
      (libsource (lib "eagle-import") (part "SMD2"))
    )
    (comp (ref "Q2")
      (value "CM7V, 32768Hz/12.5pF")
      (footprint "eagle-import:CRYSTAL2P3.2X1.5")
      (libsource (lib "eagle-import") (part "CRYSTAL2P"))
    )
    (comp (ref "Q3")
      (value "NX5032GA/32MHz/8pF")
      (footprint "eagle-import:CRYSTAL2P5.0X3.2")
      (libsource (lib "eagle-import") (part "CRYSTAL2P5.0X3.2"))
    )
    (comp (ref "R14")
      (value "1")
      (footprint "eagle-import:R0805")
      (libsource (lib "eagle-import") (part "R-EU_R0805"))
    )
    (comp (ref "C56")
      (value "10µF")
      (footprint "eagle-import:C1206")
      (libsource (lib "eagle-import") (part "resistor_C-EUC1206"))
    )
    (comp (ref "C57")
      (value "10µF")
      (footprint "eagle-import:C1206")
      (libsource (lib "eagle-import") (part "resistor_C-EUC1206"))
    )
    (comp (ref "C58")
      (value "100nF")
      (footprint "eagle-import:C0603")
      (libsource (lib "eagle-import") (part "resistor_C-EUC0603"))
    )
    (comp (ref "C59")
      (value "100nF")
      (footprint "eagle-import:C0603")
      (libsource (lib "eagle-import") (part "resistor_C-EUC0603"))
    )
    (comp (ref "C60")
      (value "100nF")
      (footprint "eagle-import:C0603")
      (libsource (lib "eagle-import") (part "resistor_C-EUC0603"))
    )
    (comp (ref "C61")
      (value "1nF")
      (footprint "eagle-import:C0603")
      (libsource (lib "eagle-import") (part "resistor_C-EUC0603"))
    )
    (comp (ref "C62")
      (value "1nF")
      (footprint "eagle-import:C0603")
      (libsource (lib "eagle-import") (part "resistor_C-EUC0603"))
    )
    (comp (ref "IC5")
      (value "LTC6102IDD-1")
      (footprint "eagle-import:DFN8-LEAD")
      (libsource (lib "eagle-import") (part "LTC6102IDD-1"))
    )
    (comp (ref "IC6")
      (value "LTC6102IDD-1")
      (footprint "eagle-import:DFN8-LEAD")
      (libsource (lib "eagle-import") (part "LTC6102IDD-1"))
    )
    (comp (ref "R64")
      (value "150")
      (footprint "eagle-import:R0805")
      (libsource (lib "eagle-import") (part "resistor_R-EU_R0805"))
    )
    (comp (ref "R65")
      (value "150")
      (footprint "eagle-import:R0805")
      (libsource (lib "eagle-import") (part "resistor_R-EU_R0805"))
    )
    (comp (ref "R66")
      (value "100K")
      (footprint "eagle-import:R0805")
      (libsource (lib "eagle-import") (part "resistor_R-EU_R0805"))
    )
    (comp (ref "R67")
      (value "100K")
      (footprint "eagle-import:R0805")
      (libsource (lib "eagle-import") (part "resistor_R-EU_R0805"))
    )
    (comp (ref "R68")
      (value "100")
      (footprint "eagle-import:R0805")
      (libsource (lib "eagle-import") (part "resistor_R-EU_R0805"))
    )
    (comp (ref "R69")
      (value "100K")
      (footprint "eagle-import:R0805")
      (libsource (lib "eagle-import") (part "resistor_R-EU_R0805"))
    )
    (comp (ref "R70")
      (value "100K")
      (footprint "eagle-import:R0805")
      (libsource (lib "eagle-import") (part "resistor_R-EU_R0805"))
    )
    (comp (ref "R71")
      (value "100")
      (footprint "eagle-import:R0805")
      (libsource (lib "eagle-import") (part "resistor_R-EU_R0805"))
    )
    (comp (ref "R72")
      (value "40K")
      (footprint "eagle-import:R0805")
      (libsource (lib "eagle-import") (part "resistor_R-EU_R0805"))
    )
    (comp (ref "R73")
      (value "40K")
      (footprint "eagle-import:R0805")
      (libsource (lib "eagle-import") (part "resistor_R-EU_R0805"))
    )
    (comp (ref "R74")
      (value "100K")
      (footprint "eagle-import:R0805")
      (libsource (lib "eagle-import") (part "resistor_R-EU_R0805"))
    )
    (comp (ref "R75")
      (value "100K")
      (footprint "eagle-import:R0805")
      (libsource (lib "eagle-import") (part "resistor_R-EU_R0805"))
    )
    (comp (ref "R76")
      (value "100")
      (footprint "eagle-import:R0805")
      (libsource (lib "eagle-import") (part "resistor_R-EU_R0805"))
    )
    (comp (ref "R77")
      (value "300K")
      (footprint "eagle-import:R0805")
      (libsource (lib "eagle-import") (part "resistor_R-EU_R0805"))
    )
    (comp (ref "R78")
      (value "100K")
      (footprint "eagle-import:R0805")
      (libsource (lib "eagle-import") (part "resistor_R-EU_R0805"))
    )
    (comp (ref "R79")
      (value "100")
      (footprint "eagle-import:R0805")
      (libsource (lib "eagle-import") (part "resistor_R-EU_R0805"))
    )
    (comp (ref "R80")
      (value "100K")
      (footprint "eagle-import:R0805")
      (libsource (lib "eagle-import") (part "resistor_R-EU_R0805"))
    )
    (comp (ref "R81")
      (value "100K")
      (footprint "eagle-import:R0805")
      (libsource (lib "eagle-import") (part "resistor_R-EU_R0805"))
    )
    (comp (ref "R82")
      (value "100")
      (footprint "eagle-import:R0805")
      (libsource (lib "eagle-import") (part "resistor_R-EU_R0805"))
    )
    (comp (ref "R83")
      (value "300K")
      (footprint "eagle-import:R0805")
      (libsource (lib "eagle-import") (part "resistor_R-EU_R0805"))
    )
    (comp (ref "R84")
      (value "100K")
      (footprint "eagle-import:R0805")
      (libsource (lib "eagle-import") (part "resistor_R-EU_R0805"))
    )
    (comp (ref "R85")
      (value "100")
      (footprint "eagle-import:R0805")
      (libsource (lib "eagle-import") (part "resistor_R-EU_R0805"))
    )
    (comp (ref "R86")
      (value "100K")
      (footprint "eagle-import:R0805")
      (libsource (lib "eagle-import") (part "resistor_R-EU_R0805"))
    )
    (comp (ref "T3")
      (value "2N7002")
      (footprint "eagle-import:ZETEX_SOT-23")
      (libsource (lib "eagle-import") (part "ZETEX_NMOSSOT23"))
    )
    (comp (ref "T4")
      (value "FDN358P")
      (footprint "eagle-import:ZETEX_SOT-23")
      (libsource (lib "eagle-import") (part "ZETEX_PMOSSOT23"))
    )
    (comp (ref "T5")
      (value "2N7002")
      (footprint "eagle-import:ZETEX_SOT-23")
      (libsource (lib "eagle-import") (part "ZETEX_NMOSSOT23"))
    )
    (comp (ref "T6")
      (value "FDN358P")
      (footprint "eagle-import:ZETEX_SOT-23")
      (libsource (lib "eagle-import") (part "ZETEX_PMOSSOT23"))
    )
    (comp (ref "T7")
      (value "2N7002")
      (footprint "eagle-import:ZETEX_SOT-23")
      (libsource (lib "eagle-import") (part "ZETEX_NMOSSOT23"))
    )
    (comp (ref "T8")
      (value "FDN358P")
      (footprint "eagle-import:ZETEX_SOT-23")
      (libsource (lib "eagle-import") (part "ZETEX_PMOSSOT23"))
    )
  )
  (nets
    (net (code "1") (name "AVDD") (class "Default")
      (node (ref "C19") (pin "2") (pinfunction "2_2") (pintype "passive"))
      (node (ref "C21") (pin "2") (pinfunction "2_2") (pintype "passive"))
      (node (ref "C23") (pin "2") (pinfunction "2_2") (pintype "passive"))
      (node (ref "IC2") (pin "23") (pinfunction "AVDD_1_23") (pintype "power_in"))
      (node (ref "IC2") (pin "27") (pinfunction "AVDD_0_27") (pintype "power_in"))
      (node (ref "R14") (pin "2") (pinfunction "2_2") (pintype "passive"))
    )
    (net (code "2") (name "BATT_INPUT") (class "Default")
      (node (ref "C1") (pin "+") (pinfunction "+_+") (pintype "passive"))
      (node (ref "C2") (pin "1") (pinfunction "1_1") (pintype "passive"))
      (node (ref "F1") (pin "P$2") (pinfunction "2_P$2") (pintype "passive"))
      (node (ref "F4") (pin "P$1") (pinfunction "1_P$1") (pintype "passive"))
      (node (ref "F5") (pin "P$1") (pinfunction "1_P$1") (pintype "passive"))
      (node (ref "IC1") (pin "2") (pinfunction "VIN_2") (pintype "passive"))
      (node (ref "Q1") (pin "1") (pinfunction "S_1") (pintype "passive"))
      (node (ref "Q1") (pin "2") (pinfunction "S_2") (pintype "passive"))
      (node (ref "Q1") (pin "3") (pinfunction "S_3") (pintype "passive"))
      (node (ref "R7") (pin "2") (pinfunction "2_2") (pintype "passive"))
    )
    (net (code "3") (name "BATT_OUTPUT") (class "Default")
      (node (ref "C60") (pin "1") (pinfunction "1_1") (pintype "passive"))
      (node (ref "R75") (pin "2") (pinfunction "2_2") (pintype "passive"))
      (node (ref "T4") (pin "1") (pinfunction "D_1") (pintype "passive"))
      (node (ref "X2") (pin "3") (pinfunction "1_3") (pintype "passive"))
    )
    (net (code "4") (name "BATT_UE") (class "Default")
      (node (ref "F1") (pin "P$1") (pinfunction "1_P$1") (pintype "passive"))
      (node (ref "R69") (pin "2") (pinfunction "2_2") (pintype "passive"))
      (node (ref "T4") (pin "2") (pinfunction "S_2") (pintype "passive"))
    )
    (net (code "5") (name "GND") (class "Default")
      (node (ref "C1") (pin "-") (pinfunction "-_-") (pintype "passive"))
      (node (ref "C10") (pin "1") (pinfunction "1_1") (pintype "passive"))
      (node (ref "C11") (pin "1") (pinfunction "1_1") (pintype "passive"))
      (node (ref "C12") (pin "1") (pinfunction "1_1") (pintype "passive"))
      (node (ref "C13") (pin "1") (pinfunction "1_1") (pintype "passive"))
      (node (ref "C14") (pin "1") (pinfunction "1_1") (pintype "passive"))
      (node (ref "C15") (pin "1") (pinfunction "1_1") (pintype "passive"))
      (node (ref "C16") (pin "1") (pinfunction "1_1") (pintype "passive"))
      (node (ref "C17") (pin "1") (pinfunction "1_1") (pintype "passive"))
      (node (ref "C18") (pin "1") (pinfunction "1_1") (pintype "passive"))
      (node (ref "C19") (pin "1") (pinfunction "1_1") (pintype "passive"))
      (node (ref "C2") (pin "2") (pinfunction "2_2") (pintype "passive"))
      (node (ref "C20") (pin "1") (pinfunction "1_1") (pintype "passive"))
      (node (ref "C21") (pin "1") (pinfunction "1_1") (pintype "passive"))
      (node (ref "C22") (pin "1") (pinfunction "1_1") (pintype "passive"))
      (node (ref "C23") (pin "1") (pinfunction "1_1") (pintype "passive"))
      (node (ref "C24") (pin "1") (pinfunction "1_1") (pintype "passive"))
      (node (ref "C25") (pin "1") (pinfunction "1_1") (pintype "passive"))
      (node (ref "C26") (pin "1") (pinfunction "1_1") (pintype "passive"))
      (node (ref "C27") (pin "1") (pinfunction "1_1") (pintype "passive"))
      (node (ref "C28") (pin "1") (pinfunction "1_1") (pintype "passive"))
      (node (ref "C29") (pin "1") (pinfunction "1_1") (pintype "passive"))
      (node (ref "C3") (pin "2") (pinfunction "2_2") (pintype "passive"))
      (node (ref "C30") (pin "1") (pinfunction "1_1") (pintype "passive"))
      (node (ref "C31") (pin "1") (pinfunction "1_1") (pintype "passive"))
      (node (ref "C32") (pin "2") (pinfunction "2_2") (pintype "passive"))
      (node (ref "C33") (pin "2") (pinfunction "2_2") (pintype "passive"))
      (node (ref "C34") (pin "2") (pinfunction "2_2") (pintype "passive"))
      (node (ref "C35") (pin "2") (pinfunction "2_2") (pintype "passive"))
      (node (ref "C36") (pin "2") (pinfunction "2_2") (pintype "passive"))
      (node (ref "C37") (pin "2") (pinfunction "2_2") (pintype "passive"))
      (node (ref "C38") (pin "2") (pinfunction "2_2") (pintype "passive"))
      (node (ref "C39") (pin "2") (pinfunction "2_2") (pintype "passive"))
      (node (ref "C4") (pin "-") (pinfunction "-_-") (pintype "passive"))
      (node (ref "C42") (pin "2") (pinfunction "2_2") (pintype "passive"))
      (node (ref "C43") (pin "2") (pinfunction "2_2") (pintype "passive"))
      (node (ref "C44") (pin "2") (pinfunction "2_2") (pintype "passive"))
      (node (ref "C45") (pin "2") (pinfunction "2_2") (pintype "passive"))
      (node (ref "C46") (pin "2") (pinfunction "2_2") (pintype "passive"))
      (node (ref "C47") (pin "2") (pinfunction "2_2") (pintype "passive"))
      (node (ref "C48") (pin "2") (pinfunction "2_2") (pintype "passive"))
      (node (ref "C49") (pin "2") (pinfunction "2_2") (pintype "passive"))
      (node (ref "C5") (pin "-") (pinfunction "-_-") (pintype "passive"))
      (node (ref "C50") (pin "2") (pinfunction "2_2") (pintype "passive"))
      (node (ref "C51") (pin "2") (pinfunction "2_2") (pintype "passive"))
      (node (ref "C52") (pin "2") (pinfunction "2_2") (pintype "passive"))
      (node (ref "C53") (pin "2") (pinfunction "2_2") (pintype "passive"))
      (node (ref "C54") (pin "2") (pinfunction "2_2") (pintype "passive"))
      (node (ref "C55") (pin "2") (pinfunction "2_2") (pintype "passive"))
      (node (ref "C56") (pin "1") (pinfunction "1_1") (pintype "passive"))
      (node (ref "C57") (pin "1") (pinfunction "1_1") (pintype "passive"))
      (node (ref "C6") (pin "-") (pinfunction "-_-") (pintype "passive"))
      (node (ref "C60") (pin "2") (pinfunction "2_2") (pintype "passive"))
      (node (ref "C61") (pin "2") (pinfunction "2_2") (pintype "passive"))
      (node (ref "C62") (pin "2") (pinfunction "2_2") (pintype "passive"))
      (node (ref "C63") (pin "2") (pinfunction "2_2") (pintype "passive"))
      (node (ref "C7") (pin "2") (pinfunction "2_2") (pintype "passive"))
      (node (ref "C8") (pin "2") (pinfunction "2_2") (pintype "passive"))
      (node (ref "C9") (pin "1") (pinfunction "1_1") (pintype "passive"))
      (node (ref "D4") (pin "A") (pinfunction "A_A") (pintype "passive"))
      (node (ref "D5") (pin "A") (pinfunction "A_A") (pintype "passive"))
      (node (ref "IC1") (pin "1") (pinfunction "GND_1") (pintype "passive"))
      (node (ref "IC1") (pin "EXP") (pinfunction "EXP_EXP") (pintype "passive"))
      (node (ref "IC2") (pin "65") (pinfunction "VSS_65") (pintype "power_in"))
      (node (ref "IC3") (pin "9") (pinfunction "GND_9") (pintype "power_in"))
      (node (ref "IC3") (pin "EXP") (pinfunction "EXP_EXP") (pintype "power_in"))
      (node (ref "IC4") (pin "9") (pinfunction "GND_9") (pintype "power_in"))
      (node (ref "IC4") (pin "EXP") (pinfunction "EXP_EXP") (pintype "power_in"))
      (node (ref "IC5") (pin "5") (pinfunction "V-_5") (pintype "passive"))
      (node (ref "IC5") (pin "EXP") (pinfunction "EXP_EXP") (pintype "passive"))
      (node (ref "IC6") (pin "5") (pinfunction "V-_5") (pintype "passive"))
      (node (ref "IC6") (pin "EXP") (pinfunction "EXP_EXP") (pintype "passive"))
      (node (ref "J1") (pin "P$1") (pinfunction "1-SLEEVE_P$1") (pintype "bidirectional"))
      (node (ref "LCD1") (pin "27") (pinfunction "GND_27") (pintype "power_in"))
      (node (ref "LCD1") (pin "38") (pinfunction "~{CSB}_38") (pintype "input"))
      (node (ref "LED1") (pin "C") (pinfunction "C_C") (pintype "passive"))
      (node (ref "LED2") (pin "C") (pinfunction "C_C") (pintype "passive"))
      (node (ref "LED8") (pin "C") (pinfunction "C_C") (pintype "passive"))
      (node (ref "LED9") (pin "C") (pinfunction "C_C") (pintype "passive"))
      (node (ref "R12") (pin "1") (pinfunction "1_1") (pintype "passive"))
      (node (ref "R28") (pin "2") (pinfunction "2_2") (pintype "passive"))
      (node (ref "R29") (pin "2") (pinfunction "2_2") (pintype "passive"))
      (node (ref "R30") (pin "2") (pinfunction "2_2") (pintype "passive"))
      (node (ref "R31") (pin "2") (pinfunction "2_2") (pintype "passive"))
      (node (ref "R32") (pin "2") (pinfunction "2_2") (pintype "passive"))
      (node (ref "R33") (pin "2") (pinfunction "2_2") (pintype "passive"))
      (node (ref "R36") (pin "1") (pinfunction "1_1") (pintype "passive"))
      (node (ref "R43") (pin "1") (pinfunction "1_1") (pintype "passive"))
      (node (ref "R46") (pin "1") (pinfunction "1_1") (pintype "passive"))
      (node (ref "R47") (pin "1") (pinfunction "1_1") (pintype "passive"))
      (node (ref "R48") (pin "1") (pinfunction "1_1") (pintype "passive"))
      (node (ref "R49") (pin "1") (pinfunction "1_1") (pintype "passive"))
      (node (ref "R5") (pin "1") (pinfunction "1_1") (pintype "passive"))
      (node (ref "R58") (pin "1") (pinfunction "1_1") (pintype "passive"))
      (node (ref "R61") (pin "1") (pinfunction "1_1") (pintype "passive"))
      (node (ref "R66") (pin "2") (pinfunction "2_2") (pintype "passive"))
      (node (ref "R67") (pin "2") (pinfunction "2_2") (pintype "passive"))
      (node (ref "R70") (pin "1") (pinfunction "1_1") (pintype "passive"))
      (node (ref "R72") (pin "2") (pinfunction "2_2") (pintype "passive"))
      (node (ref "R73") (pin "2") (pinfunction "2_2") (pintype "passive"))
      (node (ref "R75") (pin "1") (pinfunction "1_1") (pintype "passive"))
      (node (ref "R78") (pin "1") (pinfunction "1_1") (pintype "passive"))
      (node (ref "R80") (pin "1") (pinfunction "1_1") (pintype "passive"))
      (node (ref "R84") (pin "1") (pinfunction "1_1") (pintype "passive"))
      (node (ref "R86") (pin "1") (pinfunction "1_1") (pintype "passive"))
      (node (ref "R89") (pin "1") (pinfunction "1_1") (pintype "passive"))
      (node (ref "R9") (pin "1") (pinfunction "1_1") (pintype "passive"))
      (node (ref "R91") (pin "1") (pinfunction "1_1") (pintype "passive"))
      (node (ref "SD1") (pin "3") (pinfunction "3_3") (pintype "bidirectional"))
      (node (ref "SD1") (pin "6") (pinfunction "6_6") (pintype "bidirectional"))
      (node (ref "SD1") (pin "COM") (pinfunction "COM_COM") (pintype "passive"))
      (node (ref "T1") (pin "2") (pinfunction "S_2") (pintype "passive"))
      (node (ref "T3") (pin "2") (pinfunction "S_2") (pintype "passive"))
      (node (ref "T5") (pin "2") (pinfunction "S_2") (pintype "passive"))
      (node (ref "T7") (pin "2") (pinfunction "S_2") (pintype "passive"))
      (node (ref "T9") (pin "2") (pinfunction "S_2") (pintype "passive"))
      (node (ref "X1") (pin "1") (pinfunction "1_1") (pintype "passive"))
      (node (ref "X2") (pin "1") (pinfunction "1_1") (pintype "passive"))
      (node (ref "X2") (pin "4") (pinfunction "1_4") (pintype "passive"))
      (node (ref "X2") (pin "6") (pinfunction "1_6") (pintype "passive"))
      (node (ref "X2") (pin "8") (pinfunction "1_8") (pintype "passive"))
      (node (ref "X3") (pin "3") (pinfunction "1_3") (pintype "passive"))
      (node (ref "X4") (pin "3") (pinfunction "1_3") (pintype "passive"))
      (node (ref "X5") (pin "3") (pinfunction "3_3") (pintype "passive"))
      (node (ref "X5") (pin "5") (pinfunction "5_5") (pintype "passive"))
    )
    (net (code "6") (name "IC4_IA1_+IN") (class "Default")
      (node (ref "C34") (pin "1") (pinfunction "1_1") (pintype "passive"))
      (node (ref "C36") (pin "1") (pinfunction "1_1") (pintype "passive"))
      (node (ref "D6") (pin "A") (pinfunction "A_A") (pintype "passive"))
      (node (ref "IC6") (pin "8") (pinfunction "+IN_8") (pintype "input"))
      (node (ref "R44") (pin "2") (pinfunction "2_2") (pintype "passive"))
    )
    (net (code "7") (name "IC4_IA1_-IN") (class "Default")
      (node (ref "C56") (pin "2") (pinfunction "2_2") (pintype "passive"))
      (node (ref "C58") (pin "2") (pinfunction "2_2") (pintype "passive"))
      (node (ref "F4") (pin "P$2") (pinfunction "2_P$2") (pintype "passive"))
      (node (ref "IC6") (pin "7") (pinfunction "V+_7") (pintype "passive"))
      (node (ref "R44") (pin "1") (pinfunction "1_1") (pintype "passive"))
      (node (ref "R64") (pin "2") (pinfunction "2_2") (pintype "passive"))
    )
    (net (code "8") (name "IC5_IA2_+IN") (class "Default")
      (node (ref "C35") (pin "1") (pinfunction "1_1") (pintype "passive"))
      (node (ref "C37") (pin "1") (pinfunction "1_1") (pintype "passive"))
      (node (ref "D7") (pin "A") (pinfunction "A_A") (pintype "passive"))
      (node (ref "IC5") (pin "8") (pinfunction "+IN_8") (pintype "input"))
      (node (ref "R45") (pin "2") (pinfunction "2_2") (pintype "passive"))
    )
    (net (code "9") (name "IC5_IA2_-IN") (class "Default")
      (node (ref "C57") (pin "2") (pinfunction "2_2") (pintype "passive"))
      (node (ref "C59") (pin "2") (pinfunction "2_2") (pintype "passive"))
      (node (ref "F5") (pin "P$2") (pinfunction "2_P$2") (pintype "passive"))
      (node (ref "IC5") (pin "7") (pinfunction "V+_7") (pintype "passive"))
      (node (ref "R45") (pin "1") (pinfunction "1_1") (pintype "passive"))
      (node (ref "R65") (pin "2") (pinfunction "2_2") (pintype "passive"))
    )
    (net (code "10") (name "LCD_+3.3V") (class "Default")
      (node (ref "C63") (pin "1") (pinfunction "1_1") (pintype "passive"))
      (node (ref "C65") (pin "2") (pinfunction "2_2") (pintype "passive"))
      (node (ref "LCD1") (pin "23") (pinfunction "PSB_23") (pintype "input"))
      (node (ref "LCD1") (pin "25") (pinfunction "VIN_25") (pintype "passive"))
      (node (ref "LCD1") (pin "26") (pinfunction "VDD_26") (pintype "power_in"))
      (node (ref "LCD1") (pin "40") (pinfunction "~{RESET}_40") (pintype "input"))
      (node (ref "R91") (pin "2") (pinfunction "2_2") (pintype "passive"))
      (node (ref "T10") (pin "1") (pinfunction "D_1") (pintype "passive"))
    )
    (net (code "11") (name "MCU_RESET") (class "Default")
      (node (ref "C10") (pin "2") (pinfunction "2_2") (pintype "passive"))
      (node (ref "C31") (pin "2") (pinfunction "2_2") (pintype "passive"))
      (node (ref "IC2") (pin "20") (pinfunction "RESETN_20") (pintype "passive"))
      (node (ref "R27") (pin "1") (pinfunction "1_1") (pintype "passive"))
      (node (ref "S6") (pin "1") (pinfunction "1_1") (pintype "passive"))
      (node (ref "S6") (pin "2") (pinfunction "2_2") (pintype "passive"))
      (node (ref "X5") (pin "8") (pinfunction "8_8") (pintype "passive"))
    )
    (net (code "12") (name "Net-(C46-Pad1)") (class "Default")
      (node (ref "C46") (pin "1") (pinfunction "1_1") (pintype "passive"))
      (node (ref "C48") (pin "1") (pinfunction "1_1") (pintype "passive"))
      (node (ref "R54") (pin "1") (pinfunction "1_1") (pintype "passive"))
    )
    (net (code "13") (name "Net-(C47-Pad1)") (class "Default")
      (node (ref "C47") (pin "1") (pinfunction "1_1") (pintype "passive"))
      (node (ref "C49") (pin "1") (pinfunction "1_1") (pintype "passive"))
      (node (ref "R55") (pin "1") (pinfunction "1_1") (pintype "passive"))
    )
    (net (code "14") (name "Net-(D1-A1)") (class "Default")
      (node (ref "C3") (pin "1") (pinfunction "1_1") (pintype "passive"))
      (node (ref "D1") (pin "2") (pinfunction "A1_2") (pintype "passive"))
      (node (ref "D1") (pin "3") (pinfunction "A2_3") (pintype "passive"))
      (node (ref "D2") (pin "2") (pinfunction "A1_2") (pintype "passive"))
      (node (ref "D2") (pin "3") (pinfunction "A2_3") (pintype "passive"))
      (node (ref "D3") (pin "2") (pinfunction "A1_2") (pintype "passive"))
      (node (ref "IC1") (pin "6") (pinfunction "VOS_6") (pintype "input"))
      (node (ref "L1") (pin "2") (pinfunction "2_2") (pintype "passive"))
      (node (ref "R10") (pin "1") (pinfunction "1_1") (pintype "passive"))
      (node (ref "R11") (pin "2") (pinfunction "2_2") (pintype "passive"))
    )
    (net (code "15") (name "Net-(D3-A2)") (class "Default")
      (node (ref "C4") (pin "+") (pinfunction "+_+") (pintype "passive"))
      (node (ref "D3") (pin "3") (pinfunction "A2_3") (pintype "passive"))
      (node (ref "R13") (pin "2") (pinfunction "2_2") (pintype "passive"))
    )
    (net (code "16") (name "Net-(IC1-EN)") (class "Default")
      (node (ref "IC1") (pin "3") (pinfunction "EN_3") (pintype "input"))
      (node (ref "R7") (pin "1") (pinfunction "1_1") (pintype "passive"))
      (node (ref "R8") (pin "2") (pinfunction "2_2") (pintype "passive"))
    )
    (net (code "17") (name "Net-(IC1-ENHYS)") (class "Default")
      (node (ref "IC1") (pin "4") (pinfunction "ENHYS_4") (pintype "output"))
      (node (ref "R8") (pin "1") (pinfunction "1_1") (pintype "passive"))
      (node (ref "R9") (pin "2") (pinfunction "2_2") (pintype "passive"))
    )
    (net (code "18") (name "Net-(IC1-FB)") (class "Default")
      (node (ref "IC1") (pin "5") (pinfunction "FB_5") (pintype "input"))
      (node (ref "R11") (pin "1") (pinfunction "1_1") (pintype "passive"))
      (node (ref "R12") (pin "2") (pinfunction "2_2") (pintype "passive"))
    )
    (net (code "19") (name "Net-(IC1-SW)") (class "Default")
      (node (ref "IC1") (pin "7") (pinfunction "SW_7") (pintype "output"))
      (node (ref "L1") (pin "1") (pinfunction "1_1") (pintype "passive"))
    )
    (net (code "20") (name "Net-(IC2B-PB12{slash}DAC0_OUT1{slash}OPAMP_OUT1{slash}LETIM0_OUT1#1)") (class "Default")
      (node (ref "IC2") (pin "22") (pinfunction "PB12/DAC0_OUT1/OPAMP_OUT1/LETIM0_OUT1#1_22") (pintype "bidirectional"))
      (node (ref "PAD1") (pin "1") (pinfunction "P_1") (pintype "passive"))
    )
    (net (code "21") (name "Net-(IC2G-DECOUPLE)") (class "Default")
      (node (ref "C11") (pin "2") (pinfunction "2_2") (pintype "passive"))
      (node (ref "IC2") (pin "40") (pinfunction "DECOUPLE_40") (pintype "power_in"))
    )
    (net (code "22") (name "Net-(IC3-BOOT)") (class "Default")
      (node (ref "C40") (pin "2") (pinfunction "2_2") (pintype "passive"))
      (node (ref "IC3") (pin "1") (pinfunction "BOOT_1") (pintype "output"))
    )
    (net (code "23") (name "Net-(IC3-COMP)") (class "Default")
      (node (ref "C42") (pin "1") (pinfunction "1_1") (pintype "passive"))
      (node (ref "C44") (pin "1") (pinfunction "1_1") (pintype "passive"))
      (node (ref "IC3") (pin "8") (pinfunction "COMP_8") (pintype "input"))
      (node (ref "R52") (pin "1") (pinfunction "1_1") (pintype "passive"))
    )
    (net (code "24") (name "Net-(IC3-PH)") (class "Default")
      (node (ref "C40") (pin "1") (pinfunction "1_1") (pintype "passive"))
      (node (ref "D4") (pin "C") (pinfunction "C_C") (pintype "passive"))
      (node (ref "IC3") (pin "10") (pinfunction "PH_10") (pintype "output"))
      (node (ref "L3") (pin "1") (pinfunction "1_1") (pintype "passive"))
    )
    (net (code "25") (name "Net-(IC3-RT{slash}CLK)") (class "Default")
      (node (ref "IC3") (pin "5") (pinfunction "RT/CLK_5") (pintype "input"))
      (node (ref "R50") (pin "2") (pinfunction "2_2") (pintype "passive"))
    )
    (net (code "26") (name "Net-(IC3-SS{slash}TR)") (class "Default")
      (node (ref "C38") (pin "1") (pinfunction "1_1") (pintype "passive"))
      (node (ref "IC3") (pin "4") (pinfunction "SS/TR_4") (pintype "input"))
    )
    (net (code "27") (name "Net-(IC3-VIN)") (class "Default")
      (node (ref "D6") (pin "C") (pinfunction "C_C") (pintype "passive"))
      (node (ref "IC3") (pin "2") (pinfunction "VIN_2") (pintype "input"))
    )
    (net (code "28") (name "Net-(IC3-VSNS)") (class "Default")
      (node (ref "IC3") (pin "7") (pinfunction "VSNS_7") (pintype "input"))
      (node (ref "R57") (pin "1") (pinfunction "1_1") (pintype "passive"))
      (node (ref "R58") (pin "2") (pinfunction "2_2") (pintype "passive"))
    )
    (net (code "29") (name "Net-(IC4-BOOT)") (class "Default")
      (node (ref "C41") (pin "2") (pinfunction "2_2") (pintype "passive"))
      (node (ref "IC4") (pin "1") (pinfunction "BOOT_1") (pintype "output"))
    )
    (net (code "30") (name "Net-(IC4-COMP)") (class "Default")
      (node (ref "C43") (pin "1") (pinfunction "1_1") (pintype "passive"))
      (node (ref "C45") (pin "1") (pinfunction "1_1") (pintype "passive"))
      (node (ref "IC4") (pin "8") (pinfunction "COMP_8") (pintype "input"))
      (node (ref "R53") (pin "1") (pinfunction "1_1") (pintype "passive"))
    )
    (net (code "31") (name "Net-(IC4-PH)") (class "Default")
      (node (ref "C41") (pin "1") (pinfunction "1_1") (pintype "passive"))
      (node (ref "D5") (pin "C") (pinfunction "C_C") (pintype "passive"))
      (node (ref "IC4") (pin "10") (pinfunction "PH_10") (pintype "output"))
      (node (ref "L4") (pin "1") (pinfunction "1_1") (pintype "passive"))
    )
    (net (code "32") (name "Net-(IC4-RT{slash}CLK)") (class "Default")
      (node (ref "IC4") (pin "5") (pinfunction "RT/CLK_5") (pintype "input"))
      (node (ref "R51") (pin "2") (pinfunction "2_2") (pintype "passive"))
    )
    (net (code "33") (name "Net-(IC4-SS{slash}TR)") (class "Default")
      (node (ref "C39") (pin "1") (pinfunction "1_1") (pintype "passive"))
      (node (ref "IC4") (pin "4") (pinfunction "SS/TR_4") (pintype "input"))
    )
    (net (code "34") (name "Net-(IC4-VIN)") (class "Default")
      (node (ref "D7") (pin "C") (pinfunction "C_C") (pintype "passive"))
      (node (ref "IC4") (pin "2") (pinfunction "VIN_2") (pintype "input"))
    )
    (net (code "35") (name "Net-(IC4-VSNS)") (class "Default")
      (node (ref "IC4") (pin "7") (pinfunction "VSNS_7") (pintype "input"))
      (node (ref "R60") (pin "1") (pinfunction "1_1") (pintype "passive"))
      (node (ref "R61") (pin "2") (pinfunction "2_2") (pintype "passive"))
    )
    (net (code "36") (name "Net-(IC5-+INF)") (class "Default")
      (node (ref "IC5") (pin "1") (pinfunction "-INS_1") (pintype "input"))
      (node (ref "IC5") (pin "2") (pinfunction "+INF_2") (pintype "input"))
      (node (ref "R65") (pin "1") (pinfunction "1_1") (pintype "passive"))
    )
    (net (code "37") (name "Net-(IC5-VREG)") (class "Default")
      (node (ref "C59") (pin "1") (pinfunction "1_1") (pintype "passive"))
      (node (ref "IC5") (pin "6") (pinfunction "VREG_6") (pintype "passive"))
    )
    (net (code "38") (name "Net-(IC6-+INF)") (class "Default")
      (node (ref "IC6") (pin "1") (pinfunction "-INS_1") (pintype "input"))
      (node (ref "IC6") (pin "2") (pinfunction "+INF_2") (pintype "input"))
      (node (ref "R64") (pin "1") (pinfunction "1_1") (pintype "passive"))
    )
    (net (code "39") (name "Net-(IC6-VREG)") (class "Default")
      (node (ref "C58") (pin "1") (pinfunction "1_1") (pintype "passive"))
      (node (ref "IC6") (pin "6") (pinfunction "VREG_6") (pintype "passive"))
    )
    (net (code "40") (name "Net-(L2-Pad2)") (class "Default")
      (node (ref "L2") (pin "2") (pinfunction "2_2") (pintype "passive"))
      (node (ref "R14") (pin "1") (pinfunction "1_1") (pintype "passive"))
    )
    (net (code "41") (name "Net-(LCD1-CAP1N)") (class "Default")
      (node (ref "C64") (pin "1") (pinfunction "1_1") (pintype "passive"))
      (node (ref "LCD1") (pin "21") (pinfunction "CAP1N_21") (pintype "passive"))
    )
    (net (code "42") (name "Net-(LCD1-CAP1P)") (class "Default")
      (node (ref "C64") (pin "2") (pinfunction "2_2") (pintype "passive"))
      (node (ref "LCD1") (pin "22") (pinfunction "CAP1P_22") (pintype "passive"))
    )
    (net (code "43") (name "Net-(LCD1-VOUT)") (class "Default")
      (node (ref "C65") (pin "1") (pinfunction "1_1") (pintype "passive"))
      (node (ref "LCD1") (pin "24") (pinfunction "VOUT_24") (pintype "passive"))
    )
    (net (code "44") (name "Net-(LED1-PadA)") (class "Default")
      (node (ref "LED1") (pin "A") (pinfunction "A_A") (pintype "passive"))
      (node (ref "R1") (pin "2") (pinfunction "2_2") (pintype "passive"))
    )
    (net (code "45") (name "Net-(LED2-PadA)") (class "Default")
      (node (ref "LED2") (pin "A") (pinfunction "A_A") (pintype "passive"))
      (node (ref "R4") (pin "2") (pinfunction "2_2") (pintype "passive"))
    )
    (net (code "46") (name "Net-(LED3-PadA)") (class "Default")
      (node (ref "LED3") (pin "A") (pinfunction "A_A") (pintype "passive"))
      (node (ref "R15") (pin "1") (pinfunction "1_1") (pintype "passive"))
    )
    (net (code "47") (name "Net-(LED4-PadA)") (class "Default")
      (node (ref "LED4") (pin "A") (pinfunction "A_A") (pintype "passive"))
      (node (ref "R16") (pin "1") (pinfunction "1_1") (pintype "passive"))
    )
    (net (code "48") (name "Net-(LED5-PadA)") (class "Default")
      (node (ref "LED5") (pin "A") (pinfunction "A_A") (pintype "passive"))
      (node (ref "R17") (pin "1") (pinfunction "1_1") (pintype "passive"))
    )
    (net (code "49") (name "Net-(LED6-PadA)") (class "Default")
      (node (ref "LED6") (pin "A") (pinfunction "A_A") (pintype "passive"))
      (node (ref "R18") (pin "1") (pinfunction "1_1") (pintype "passive"))
    )
    (net (code "50") (name "Net-(LED7-PadA)") (class "Default")
      (node (ref "LED7") (pin "A") (pinfunction "A_A") (pintype "passive"))
      (node (ref "R19") (pin "1") (pinfunction "1_1") (pintype "passive"))
    )
    (net (code "51") (name "Net-(LED8-PadA)") (class "Default")
      (node (ref "LED8") (pin "A") (pinfunction "A_A") (pintype "passive"))
      (node (ref "R62") (pin "1") (pinfunction "1_1") (pintype "passive"))
    )
    (net (code "52") (name "Net-(LED9-PadA)") (class "Default")
      (node (ref "LED9") (pin "A") (pinfunction "A_A") (pintype "passive"))
      (node (ref "R63") (pin "1") (pinfunction "1_1") (pintype "passive"))
    )
    (net (code "53") (name "Net-(Q1-G)") (class "Default")
      (node (ref "Q1") (pin "4") (pinfunction "G_4") (pintype "passive"))
      (node (ref "R5") (pin "2") (pinfunction "2_2") (pintype "passive"))
    )
    (net (code "54") (name "Net-(R28-Pad1)") (class "Default")
      (node (ref "R28") (pin "1") (pinfunction "1_1") (pintype "passive"))
      (node (ref "S1") (pin "3") (pinfunction "3_3") (pintype "passive"))
      (node (ref "S1") (pin "4") (pinfunction "4_4") (pintype "passive"))
    )
    (net (code "55") (name "Net-(R29-Pad1)") (class "Default")
      (node (ref "R29") (pin "1") (pinfunction "1_1") (pintype "passive"))
      (node (ref "S2") (pin "3") (pinfunction "3_3") (pintype "passive"))
      (node (ref "S2") (pin "4") (pinfunction "4_4") (pintype "passive"))
    )
    (net (code "56") (name "Net-(R30-Pad1)") (class "Default")
      (node (ref "R30") (pin "1") (pinfunction "1_1") (pintype "passive"))
      (node (ref "S3") (pin "3") (pinfunction "3_3") (pintype "passive"))
      (node (ref "S3") (pin "4") (pinfunction "4_4") (pintype "passive"))
    )
    (net (code "57") (name "Net-(R31-Pad1)") (class "Default")
      (node (ref "R31") (pin "1") (pinfunction "1_1") (pintype "passive"))
      (node (ref "S4") (pin "3") (pinfunction "3_3") (pintype "passive"))
      (node (ref "S4") (pin "4") (pinfunction "4_4") (pintype "passive"))
    )
    (net (code "58") (name "Net-(R32-Pad1)") (class "Default")
      (node (ref "R32") (pin "1") (pinfunction "1_1") (pintype "passive"))
      (node (ref "S5") (pin "3") (pinfunction "3_3") (pintype "passive"))
      (node (ref "S5") (pin "4") (pinfunction "4_4") (pintype "passive"))
    )
    (net (code "59") (name "Net-(R33-Pad1)") (class "Default")
      (node (ref "R33") (pin "1") (pinfunction "1_1") (pintype "passive"))
      (node (ref "S6") (pin "3") (pinfunction "3_3") (pintype "passive"))
      (node (ref "S6") (pin "4") (pinfunction "4_4") (pintype "passive"))
    )
    (net (code "60") (name "Net-(R37-Pad1)") (class "Default")
      (node (ref "R37") (pin "1") (pinfunction "1_1") (pintype "passive"))
      (node (ref "SD1") (pin "8") (pinfunction "8_8") (pintype "bidirectional"))
    )
    (net (code "61") (name "Net-(R38-Pad1)") (class "Default")
      (node (ref "R38") (pin "1") (pinfunction "1_1") (pintype "passive"))
      (node (ref "SD1") (pin "9") (pinfunction "9_9") (pintype "bidirectional"))
    )
    (net (code "62") (name "Net-(R48-Pad2)") (class "Default")
      (node (ref "R48") (pin "2") (pinfunction "2_2") (pintype "passive"))
      (node (ref "R50") (pin "1") (pinfunction "1_1") (pintype "passive"))
    )
    (net (code "63") (name "Net-(R49-Pad2)") (class "Default")
      (node (ref "R49") (pin "2") (pinfunction "2_2") (pintype "passive"))
      (node (ref "R51") (pin "1") (pinfunction "1_1") (pintype "passive"))
    )
    (net (code "64") (name "Net-(R52-Pad2)") (class "Default")
      (node (ref "R52") (pin "2") (pinfunction "2_2") (pintype "passive"))
      (node (ref "R54") (pin "2") (pinfunction "2_2") (pintype "passive"))
    )
    (net (code "65") (name "Net-(R53-Pad2)") (class "Default")
      (node (ref "R53") (pin "2") (pinfunction "2_2") (pintype "passive"))
      (node (ref "R55") (pin "2") (pinfunction "2_2") (pintype "passive"))
    )
    (net (code "66") (name "Net-(R56-Pad1)") (class "Default")
      (node (ref "R56") (pin "1") (pinfunction "1_1") (pintype "passive"))
      (node (ref "R57") (pin "2") (pinfunction "2_2") (pintype "passive"))
    )
    (net (code "67") (name "Net-(R59-Pad1)") (class "Default")
      (node (ref "R59") (pin "1") (pinfunction "1_1") (pintype "passive"))
      (node (ref "R60") (pin "2") (pinfunction "2_2") (pintype "passive"))
    )
    (net (code "68") (name "Net-(T1-D)") (class "Default")
      (node (ref "R39") (pin "1") (pinfunction "1_1") (pintype "passive"))
      (node (ref "T1") (pin "1") (pinfunction "D_1") (pintype "passive"))
    )
    (net (code "69") (name "Net-(T1-G)") (class "Default")
      (node (ref "R34") (pin "1") (pinfunction "1_1") (pintype "passive"))
      (node (ref "R36") (pin "2") (pinfunction "2_2") (pintype "passive"))
      (node (ref "T1") (pin "3") (pinfunction "G_3") (pintype "passive"))
    )
    (net (code "70") (name "Net-(T2-G)") (class "Default")
      (node (ref "R35") (pin "1") (pinfunction "1_1") (pintype "passive"))
      (node (ref "R39") (pin "2") (pinfunction "2_2") (pintype "passive"))
      (node (ref "T2") (pin "3") (pinfunction "G_3") (pintype "passive"))
    )
    (net (code "71") (name "Net-(T3-D)") (class "Default")
      (node (ref "R71") (pin "1") (pinfunction "1_1") (pintype "passive"))
      (node (ref "T3") (pin "1") (pinfunction "D_1") (pintype "passive"))
    )
    (net (code "72") (name "Net-(T3-G)") (class "Default")
      (node (ref "R68") (pin "1") (pinfunction "1_1") (pintype "passive"))
      (node (ref "R70") (pin "2") (pinfunction "2_2") (pintype "passive"))
      (node (ref "T3") (pin "3") (pinfunction "G_3") (pintype "passive"))
    )
    (net (code "73") (name "Net-(T4-G)") (class "Default")
      (node (ref "R69") (pin "1") (pinfunction "1_1") (pintype "passive"))
      (node (ref "R71") (pin "2") (pinfunction "2_2") (pintype "passive"))
      (node (ref "T4") (pin "3") (pinfunction "G_3") (pintype "passive"))
    )
    (net (code "74") (name "Net-(T5-D)") (class "Default")
      (node (ref "R79") (pin "1") (pinfunction "1_1") (pintype "passive"))
      (node (ref "T5") (pin "1") (pinfunction "D_1") (pintype "passive"))
    )
    (net (code "75") (name "Net-(T5-G)") (class "Default")
      (node (ref "R76") (pin "1") (pinfunction "1_1") (pintype "passive"))
      (node (ref "R78") (pin "2") (pinfunction "2_2") (pintype "passive"))
      (node (ref "T5") (pin "3") (pinfunction "G_3") (pintype "passive"))
    )
    (net (code "76") (name "Net-(T6-G)") (class "Default")
      (node (ref "R74") (pin "1") (pinfunction "1_1") (pintype "passive"))
      (node (ref "R79") (pin "2") (pinfunction "2_2") (pintype "passive"))
      (node (ref "T6") (pin "3") (pinfunction "G_3") (pintype "passive"))
    )
    (net (code "77") (name "Net-(T6-S)") (class "Default")
      (node (ref "R77") (pin "1") (pinfunction "1_1") (pintype "passive"))
      (node (ref "T6") (pin "2") (pinfunction "S_2") (pintype "passive"))
    )
    (net (code "78") (name "Net-(T7-D)") (class "Default")
      (node (ref "R85") (pin "1") (pinfunction "1_1") (pintype "passive"))
      (node (ref "T7") (pin "1") (pinfunction "D_1") (pintype "passive"))
    )
    (net (code "79") (name "Net-(T7-G)") (class "Default")
      (node (ref "R82") (pin "1") (pinfunction "1_1") (pintype "passive"))
      (node (ref "R84") (pin "2") (pinfunction "2_2") (pintype "passive"))
      (node (ref "T7") (pin "3") (pinfunction "G_3") (pintype "passive"))
    )
    (net (code "80") (name "Net-(T8-G)") (class "Default")
      (node (ref "R81") (pin "1") (pinfunction "1_1") (pintype "passive"))
      (node (ref "R85") (pin "2") (pinfunction "2_2") (pintype "passive"))
      (node (ref "T8") (pin "3") (pinfunction "G_3") (pintype "passive"))
    )
    (net (code "81") (name "Net-(T8-S)") (class "Default")
      (node (ref "R83") (pin "1") (pinfunction "1_1") (pintype "passive"))
      (node (ref "T8") (pin "2") (pinfunction "S_2") (pintype "passive"))
    )
    (net (code "82") (name "Net-(T9-D)") (class "Default")
      (node (ref "R90") (pin "1") (pinfunction "1_1") (pintype "passive"))
      (node (ref "T9") (pin "1") (pinfunction "D_1") (pintype "passive"))
    )
    (net (code "83") (name "Net-(T9-G)") (class "Default")
      (node (ref "R87") (pin "1") (pinfunction "1_1") (pintype "passive"))
      (node (ref "R89") (pin "2") (pinfunction "2_2") (pintype "passive"))
      (node (ref "T9") (pin "3") (pinfunction "G_3") (pintype "passive"))
    )
    (net (code "84") (name "Net-(T10-G)") (class "Default")
      (node (ref "R88") (pin "1") (pinfunction "1_1") (pintype "passive"))
      (node (ref "R90") (pin "2") (pinfunction "2_2") (pintype "passive"))
      (node (ref "T10") (pin "3") (pinfunction "G_3") (pintype "passive"))
    )
    (net (code "85") (name "Net-(X2B-1)") (class "Default")
      (node (ref "Q1") (pin "10") (pinfunction "D_10") (pintype "passive"))
      (node (ref "Q1") (pin "11") (pinfunction "D_11") (pintype "passive"))
      (node (ref "Q1") (pin "5") (pinfunction "D_5") (pintype "passive"))
      (node (ref "Q1") (pin "6") (pinfunction "D_6") (pintype "passive"))
      (node (ref "Q1") (pin "7") (pinfunction "D_7") (pintype "passive"))
      (node (ref "Q1") (pin "8") (pinfunction "D_8") (pintype "passive"))
      (node (ref "Q1") (pin "9") (pinfunction "D_9") (pintype "passive"))
      (node (ref "X2") (pin "2") (pinfunction "1_2") (pintype "passive"))
    )
    (net (code "86") (name "PA0_SMBUS_SDA") (class "Default")
      (node (ref "IC2") (pin "1") (pinfunction "PA0/I2C0_SDA#0/TIM0_CC0#0,1_1") (pintype "bidirectional"))
      (node (ref "R3") (pin "2") (pinfunction "2_2") (pintype "passive"))
      (node (ref "X1") (pin "2") (pinfunction "1_2") (pintype "passive"))
    )
    (net (code "87") (name "PA1_SMBUS_SCL") (class "Default")
      (node (ref "IC2") (pin "2") (pinfunction "PA1/CMU_CLK1#0/I2C0_SCL#0/TIM0_CC1#0,1_2") (pintype "bidirectional"))
      (node (ref "R2") (pin "2") (pinfunction "2_2") (pintype "passive"))
      (node (ref "X1") (pin "3") (pinfunction "1_3") (pintype "passive"))
    )
    (net (code "88") (name "PA2_POWER_LED") (class "Default")
      (node (ref "IC2") (pin "3") (pinfunction "PA2/CMU_CLK0#0/TIM0_CC2#0,1_3") (pintype "bidirectional"))
      (node (ref "R1") (pin "1") (pinfunction "1_1") (pintype "passive"))
    )
    (net (code "89") (name "PA3_CAM1_ENABLE") (class "Default")
      (node (ref "IC2") (pin "4") (pinfunction "PA3/TIM0_CDTI0#0_4") (pintype "bidirectional"))
      (node (ref "IC3") (pin "3") (pinfunction "ENA_3") (pintype "input"))
      (node (ref "R46") (pin "2") (pinfunction "2_2") (pintype "passive"))
    )
    (net (code "90") (name "PA4_CAM2_ENABLE") (class "Default")
      (node (ref "IC2") (pin "5") (pinfunction "PA4/TIM0_CDTI1#0_5") (pintype "bidirectional"))
      (node (ref "IC4") (pin "3") (pinfunction "ENA_3") (pintype "input"))
      (node (ref "R47") (pin "2") (pinfunction "2_2") (pintype "passive"))
    )
    (net (code "91") (name "PA5_LOG_FLUSH_LED") (class "Default")
      (node (ref "IC2") (pin "6") (pinfunction "PA5/LEU1_TX#1/TIM0_CDTI2#0_6") (pintype "bidirectional"))
      (node (ref "R4") (pin "1") (pinfunction "1_1") (pintype "passive"))
    )
    (net (code "92") (name "PA6_BATT_OUTPUT_POWER") (class "Default")
      (node (ref "IC2") (pin "7") (pinfunction "PA6/LEU1_RX#1_7") (pintype "bidirectional"))
      (node (ref "R68") (pin "2") (pinfunction "2_2") (pintype "passive"))
    )
    (net (code "93") (name "PA8_PUSHBUTTON_UP") (class "Default")
      (node (ref "C26") (pin "2") (pinfunction "2_2") (pintype "passive"))
      (node (ref "IC2") (pin "17") (pinfunction "PA8/TIM2_CC0#0_17") (pintype "bidirectional"))
      (node (ref "LED3") (pin "C") (pinfunction "C_C") (pintype "passive"))
      (node (ref "R20") (pin "1") (pinfunction "1_1") (pintype "passive"))
      (node (ref "S1") (pin "1") (pinfunction "1_1") (pintype "passive"))
      (node (ref "S1") (pin "2") (pinfunction "2_2") (pintype "passive"))
    )
    (net (code "94") (name "PA9_PUSHBUTTON_RIGHT") (class "Default")
      (node (ref "C27") (pin "2") (pinfunction "2_2") (pintype "passive"))
      (node (ref "IC2") (pin "18") (pinfunction "PA9/TIM2_CC1#0_18") (pintype "bidirectional"))
      (node (ref "LED4") (pin "C") (pinfunction "C_C") (pintype "passive"))
      (node (ref "R21") (pin "1") (pinfunction "1_1") (pintype "passive"))
      (node (ref "S2") (pin "1") (pinfunction "1_1") (pintype "passive"))
      (node (ref "S2") (pin "2") (pinfunction "2_2") (pintype "passive"))
    )
    (net (code "95") (name "PA10_PUSHBUTTON_LEFT") (class "Default")
      (node (ref "C28") (pin "2") (pinfunction "2_2") (pintype "passive"))
      (node (ref "IC2") (pin "19") (pinfunction "PA10/TIM2_CC2#0_19") (pintype "bidirectional"))
      (node (ref "LED5") (pin "C") (pinfunction "C_C") (pintype "passive"))
      (node (ref "R22") (pin "1") (pinfunction "1_1") (pintype "passive"))
      (node (ref "S3") (pin "1") (pinfunction "1_1") (pintype "passive"))
      (node (ref "S3") (pin "2") (pinfunction "2_2") (pintype "passive"))
    )
    (net (code "96") (name "PB7_LFXTAL_P") (class "Default")
      (node (ref "C17") (pin "2") (pinfunction "2_2") (pintype "passive"))
      (node (ref "IC2") (pin "15") (pinfunction "PB7/LFXTAL_P/US1_CLK#0_15") (pintype "bidirectional"))
      (node (ref "Q2") (pin "2") (pinfunction "2_2") (pintype "passive"))
    )
    (net (code "97") (name "PB8_LFXTAL_N") (class "Default")
      (node (ref "C12") (pin "2") (pinfunction "2_2") (pintype "passive"))
      (node (ref "IC2") (pin "16") (pinfunction "PB8/LFXTAL_N/US1_CS#0_16") (pintype "bidirectional"))
      (node (ref "Q2") (pin "1") (pinfunction "1_1") (pintype "passive"))
    )
    (net (code "98") (name "PB11_POWER_GOOD") (class "Default")
      (node (ref "IC1") (pin "8") (pinfunction "PG_8") (pintype "output"))
      (node (ref "IC2") (pin "21") (pinfunction "PB11/DAC0_OUT0/OPAMP_OUT0/LETIM0_OUT0#1_21") (pintype "bidirectional"))
      (node (ref "R10") (pin "2") (pinfunction "2_2") (pintype "passive"))
    )
    (net (code "99") (name "PB13_HFXTAL_P") (class "Default")
      (node (ref "C18") (pin "2") (pinfunction "2_2") (pintype "passive"))
      (node (ref "IC2") (pin "24") (pinfunction "PB13/HFXTAL_P/LEU0_TX#1_24") (pintype "bidirectional"))
      (node (ref "Q3") (pin "2") (pinfunction "2_2") (pintype "passive"))
    )
    (net (code "100") (name "PB14_HFXTAL_N") (class "Default")
      (node (ref "C13") (pin "2") (pinfunction "2_2") (pintype "passive"))
      (node (ref "IC2") (pin "25") (pinfunction "PB14/HFXTAL_N/LEU0_RX#1_25") (pintype "bidirectional"))
      (node (ref "Q3") (pin "1") (pinfunction "1_1") (pintype "passive"))
    )
    (net (code "101") (name "PC0_RFID_RX") (class "Default")
      (node (ref "IC2") (pin "9") (pinfunction "PC0/ACMP0_CH0/PCNT0_S0IN#2/US1_TX#0_9") (pintype "bidirectional"))
      (node (ref "X3") (pin "1") (pinfunction "1_1") (pintype "passive"))
    )
    (net (code "102") (name "PC1_RFID_TX") (class "Default")
      (node (ref "IC2") (pin "10") (pinfunction "PC1/ACMP0_CH1/PCNT0_S1IN#2/US1_RX#0_10") (pintype "bidirectional"))
      (node (ref "X3") (pin "2") (pinfunction "1_2") (pintype "passive"))
    )
    (net (code "103") (name "PC2_SD_SDO") (class "Default")
      (node (ref "IC2") (pin "11") (pinfunction "PC2/ACMP0_CH2/US2_TX_11") (pintype "bidirectional"))
      (node (ref "SD1") (pin "2") (pinfunction "2_2") (pintype "bidirectional"))
    )
    (net (code "104") (name "PC3_SD_SDI") (class "Default")
      (node (ref "IC2") (pin "12") (pinfunction "PC3/ACMP0_CH3/US2_RX_12") (pintype "bidirectional"))
      (node (ref "R41") (pin "1") (pinfunction "1_1") (pintype "passive"))
      (node (ref "SD1") (pin "7") (pinfunction "7_7") (pintype "bidirectional"))
    )
    (net (code "105") (name "PC4_SD_CLK") (class "Default")
      (node (ref "IC2") (pin "13") (pinfunction "PC4/ACMP0_CH4/LETIM0_OUT0#3/PCNT1_S0IN/US2_CLK_13") (pintype "bidirectional"))
      (node (ref "SD1") (pin "5") (pinfunction "5_5") (pintype "bidirectional"))
    )
    (net (code "106") (name "PC5_SD_CS") (class "Default")
      (node (ref "IC2") (pin "14") (pinfunction "PC5/ACMP0_CH5/LETIM0_OUT1#3/PCNT1_S1IN/US2_CS_14") (pintype "bidirectional"))
      (node (ref "SD1") (pin "1") (pinfunction "1_1") (pintype "bidirectional"))
    )
    (net (code "107") (name "PC6_SD_CD") (class "Default")
      (node (ref "IC2") (pin "37") (pinfunction "PC6/ACMP0_CH6/I2C0_SDA#2/LEU1_TX#0_37") (pintype "bidirectional"))
      (node (ref "R40") (pin "2") (pinfunction "2_2") (pintype "passive"))
      (node (ref "SD1") (pin "CDS") (pinfunction "CDS_CDS") (pintype "passive"))
    )
    (net (code "108") (name "PC7_SD_WP") (class "Default")
      (node (ref "IC2") (pin "38") (pinfunction "PC7/ACMP0_CH7/I2C0_SCL#2/LEU1_RX#0_38") (pintype "bidirectional"))
      (node (ref "R42") (pin "1") (pinfunction "1_1") (pintype "passive"))
      (node (ref "SD1") (pin "WPS") (pinfunction "WPS_WPS") (pintype "passive"))
    )
    (net (code "109") (name "PC8_MEASURE_ON_UA1") (class "Default")
      (node (ref "IC2") (pin "41") (pinfunction "PC8/ACMP1_CH0/TIM2_CC0#2/US0_CS#2_41") (pintype "bidirectional"))
      (node (ref "IC6") (pin "3") (pinfunction "EN_3") (pintype "input"))
      (node (ref "R67") (pin "1") (pinfunction "1_1") (pintype "passive"))
      (node (ref "R76") (pin "2") (pinfunction "2_2") (pintype "passive"))
    )
    (net (code "110") (name "PC9_MEASURE_ON_UA2") (class "Default")
      (node (ref "IC2") (pin "42") (pinfunction "PC9/ACMP1_CH1/TIM2_CC1#2/US0_CLK#2_42") (pintype "bidirectional"))
      (node (ref "IC5") (pin "3") (pinfunction "EN_3") (pintype "input"))
      (node (ref "R66") (pin "1") (pinfunction "1_1") (pintype "passive"))
      (node (ref "R82") (pin "2") (pinfunction "2_2") (pintype "passive"))
    )
    (net (code "111") (name "PC10_SD_POWER") (class "Default")
      (node (ref "IC2") (pin "43") (pinfunction "PC10/ACMP1_CH2/TIM2_CC2#2/US0_RX#2_43") (pintype "bidirectional"))
      (node (ref "R34") (pin "2") (pinfunction "2_2") (pintype "passive"))
    )
    (net (code "112") (name "PC12_SD_PULLUP") (class "Default")
      (node (ref "IC2") (pin "45") (pinfunction "PC12/ACMP1_CH4/CMU_CLK0#1_45") (pintype "bidirectional"))
      (node (ref "R40") (pin "1") (pinfunction "1_1") (pintype "passive"))
    )
    (net (code "113") (name "PC13_PUSHBUTTON_DOWN") (class "Default")
      (node (ref "C29") (pin "2") (pinfunction "2_2") (pintype "passive"))
      (node (ref "IC2") (pin "46") (pinfunction "PC13/ACMP1_CH5/PCNT0_S0IN#0/TIM0_CDTI0#1,3/TIM1_CC0#0_46") (pintype "bidirectional"))
      (node (ref "LED6") (pin "C") (pinfunction "C_C") (pintype "passive"))
      (node (ref "R23") (pin "1") (pinfunction "1_1") (pintype "passive"))
      (node (ref "S4") (pin "1") (pinfunction "1_1") (pintype "passive"))
      (node (ref "S4") (pin "2") (pinfunction "2_2") (pintype "passive"))
    )
    (net (code "114") (name "PC14_PUSHBUTTON_SET") (class "Default")
      (node (ref "C30") (pin "2") (pinfunction "2_2") (pintype "passive"))
      (node (ref "IC2") (pin "47") (pinfunction "PC14/ACMP1_CH6/PCNT0_S1IN#0/TIM0_CDTI1#1,3/TIM1_CC1#0_47") (pintype "bidirectional"))
      (node (ref "LED7") (pin "C") (pinfunction "C_C") (pintype "passive"))
      (node (ref "R24") (pin "1") (pinfunction "1_1") (pintype "passive"))
      (node (ref "S5") (pin "1") (pinfunction "1_1") (pintype "passive"))
      (node (ref "S5") (pin "2") (pinfunction "2_2") (pintype "passive"))
    )
    (net (code "115") (name "PC15_BOOTER") (class "Default")
      (node (ref "IC2") (pin "48") (pinfunction "PC15/ACMP1_CH7/DBG_SWO#1/TIM0_CDTI2#1,3/TIM1_CC2#0_48") (pintype "bidirectional"))
      (node (ref "R6") (pin "1") (pinfunction "1_1") (pintype "passive"))
    )
    (net (code "116") (name "PD0_ADC_IA1_IN") (class "Default")
      (node (ref "IC2") (pin "28") (pinfunction "PD0/ADC0_CH0/PCNT2_S0IN#0/US1_TX#1_28") (pintype "bidirectional"))
      (node (ref "IC6") (pin "4") (pinfunction "OUT_4") (pintype "output"))
      (node (ref "R72") (pin "1") (pinfunction "1_1") (pintype "passive"))
    )
    (net (code "117") (name "PD1_DCF77_ENABLE") (class "Default")
      (node (ref "IC2") (pin "29") (pinfunction "PD1/ADC0_CH1/PCNT2_S1IN#0/TIM0_CC0#3/US1_RX#1_29") (pintype "bidirectional"))
      (node (ref "X4") (pin "2") (pinfunction "1_2") (pintype "passive"))
    )
    (net (code "118") (name "PD2_DCF77_SIGNAL") (class "Default")
      (node (ref "IC2") (pin "30") (pinfunction "PD2/ADC0_CH2/TIM0_CC1#3/US1_CLK#1_30") (pintype "bidirectional"))
      (node (ref "X4") (pin "1") (pinfunction "1_1") (pintype "passive"))
    )
    (net (code "119") (name "PD3_ADC_IA2_IN") (class "Default")
      (node (ref "IC2") (pin "31") (pinfunction "PD3/ADC0_CH3/TIM0_CC2#3/US1_CS#1_31") (pintype "bidirectional"))
      (node (ref "IC5") (pin "4") (pinfunction "OUT_4") (pintype "output"))
      (node (ref "R73") (pin "1") (pinfunction "1_1") (pintype "passive"))
    )
    (net (code "120") (name "PD4_LEUART_TX") (class "Default")
      (node (ref "IC2") (pin "32") (pinfunction "PD4/ADC0_CH4/LEU0_TX#0_32") (pintype "bidirectional"))
      (node (ref "R26") (pin "1") (pinfunction "1_1") (pintype "passive"))
    )
    (net (code "121") (name "PD5_LEUART_RX") (class "Default")
      (node (ref "IC2") (pin "33") (pinfunction "PD5/ADC0_CH5/LEU0_RX#0_33") (pintype "bidirectional"))
      (node (ref "R25") (pin "1") (pinfunction "1_1") (pintype "passive"))
    )
    (net (code "122") (name "PD6_ADC_UA1_IN") (class "Default")
      (node (ref "C61") (pin "1") (pinfunction "1_1") (pintype "passive"))
      (node (ref "IC2") (pin "34") (pinfunction "PD6/ADC0_CH6/I2C0_SDA#1/LETIM0_OUT0#0_34") (pintype "bidirectional"))
      (node (ref "R80") (pin "2") (pinfunction "2_2") (pintype "passive"))
      (node (ref "T6") (pin "1") (pinfunction "D_1") (pintype "passive"))
    )
    (net (code "123") (name "PD7_ADC_UA2_IN") (class "Default")
      (node (ref "C62") (pin "1") (pinfunction "1_1") (pintype "passive"))
      (node (ref "IC2") (pin "35") (pinfunction "PD7/ADC0_CH7/I2C0_SCL#1/LETIM0_OUT1#0_35") (pintype "bidirectional"))
      (node (ref "R86") (pin "2") (pinfunction "2_2") (pintype "passive"))
      (node (ref "T8") (pin "1") (pinfunction "D_1") (pintype "passive"))
    )
    (net (code "124") (name "PD8_LCD_POWER") (class "Default")
      (node (ref "IC2") (pin "36") (pinfunction "PD8/CMU_CLK1#1_36") (pintype "bidirectional"))
      (node (ref "R87") (pin "2") (pinfunction "2_2") (pintype "passive"))
    )
    (net (code "125") (name "PE8_LCD_D0") (class "Default")
      (node (ref "IC2") (pin "56") (pinfunction "PE8/PCNT2_S0IN#1_56") (pintype "bidirectional"))
      (node (ref "LCD1") (pin "35") (pinfunction "D0_35") (pintype "bidirectional"))
    )
    (net (code "126") (name "PE9_LCD_D1") (class "Default")
      (node (ref "IC2") (pin "57") (pinfunction "PE9/PCNT2_S1IN#1_57") (pintype "bidirectional"))
      (node (ref "LCD1") (pin "34") (pinfunction "D1_34") (pintype "bidirectional"))
    )
    (net (code "127") (name "PE10_LCD_D2") (class "Default")
      (node (ref "IC2") (pin "58") (pinfunction "PE10/TIM1_CC0#1/US0_TX#0_58") (pintype "bidirectional"))
      (node (ref "LCD1") (pin "33") (pinfunction "D2_33") (pintype "bidirectional"))
    )
    (net (code "128") (name "PE11_LCD_D3") (class "Default")
      (node (ref "IC2") (pin "59") (pinfunction "PE11/TIM1_CC1#1/US0_RX#0_59") (pintype "bidirectional"))
      (node (ref "LCD1") (pin "32") (pinfunction "D3_32") (pintype "bidirectional"))
    )
    (net (code "129") (name "PE12_LCD_D4") (class "Default")
      (node (ref "IC2") (pin "60") (pinfunction "PE12/TIM1_CC2#1/US0_CLK#0_60") (pintype "bidirectional"))
      (node (ref "LCD1") (pin "31") (pinfunction "D4_31") (pintype "bidirectional"))
    )
    (net (code "130") (name "PE13_LCD_D5") (class "Default")
      (node (ref "IC2") (pin "61") (pinfunction "PE13/ACMP0_O/US0_CS#0_61") (pintype "bidirectional"))
      (node (ref "LCD1") (pin "30") (pinfunction "D5_30") (pintype "bidirectional"))
    )
    (net (code "131") (name "PE14_LCD_D6") (class "Default")
      (node (ref "IC2") (pin "62") (pinfunction "PE14/LEU0_TX#2_62") (pintype "bidirectional"))
      (node (ref "LCD1") (pin "29") (pinfunction "D6_29") (pintype "bidirectional"))
    )
    (net (code "132") (name "PE15_LCD_D7") (class "Default")
      (node (ref "IC2") (pin "63") (pinfunction "PE15/LEU0_RX#2_63") (pintype "bidirectional"))
      (node (ref "LCD1") (pin "28") (pinfunction "D7_28") (pintype "bidirectional"))
    )
    (net (code "133") (name "PF0_DBG_SWCLK") (class "Default")
      (node (ref "IC2") (pin "49") (pinfunction "PF0/DBG_SWCLK#0,1/LETIM0_OUT0#2_49") (pintype "bidirectional"))
      (node (ref "X5") (pin "4") (pinfunction "4_4") (pintype "passive"))
    )
    (net (code "134") (name "PF1_DBG_SWDIO") (class "Default")
      (node (ref "IC2") (pin "50") (pinfunction "PF1/DBG_SWDIO#0,1/LETIM0_OUT1#2_50") (pintype "bidirectional"))
      (node (ref "X5") (pin "2") (pinfunction "2_2") (pintype "passive"))
    )
    (net (code "135") (name "PF2_DBG_SWO") (class "Default")
      (node (ref "IC2") (pin "51") (pinfunction "PF2/ACMP1_O/DBG_SWO#0_51") (pintype "bidirectional"))
      (node (ref "X5") (pin "6") (pinfunction "6_6") (pintype "passive"))
    )
    (net (code "136") (name "PF3_LCD_ENABLE") (class "Default")
      (node (ref "IC2") (pin "52") (pinfunction "PF3/TIM0_CDTI0#2_52") (pintype "bidirectional"))
      (node (ref "LCD1") (pin "36") (pinfunction "E_36") (pintype "input"))
    )
    (net (code "137") (name "PF4_LCD_RW") (class "Default")
      (node (ref "IC2") (pin "53") (pinfunction "PF4/TIM0_CDTI1#2_53") (pintype "bidirectional"))
      (node (ref "LCD1") (pin "37") (pinfunction "R/~{W}_37") (pintype "input"))
    )
    (net (code "138") (name "PF5_LCD_RS") (class "Default")
      (node (ref "IC2") (pin "54") (pinfunction "PF5/TIM0_CDTI2#2_54") (pintype "bidirectional"))
      (node (ref "LCD1") (pin "39") (pinfunction "RS_39") (pintype "input"))
    )
    (net (code "139") (name "RXD_HOST") (class "Default")
      (node (ref "J1") (pin "P$3") (pinfunction "3-RIGHT_P$3") (pintype "bidirectional"))
      (node (ref "R26") (pin "2") (pinfunction "2_2") (pintype "passive"))
    )
    (net (code "140") (name "SD_+3.3V") (class "Default")
      (node (ref "C32") (pin "1") (pinfunction "1_1") (pintype "passive"))
      (node (ref "C33") (pin "1") (pinfunction "1_1") (pintype "passive"))
      (node (ref "R37") (pin "2") (pinfunction "2_2") (pintype "passive"))
      (node (ref "R38") (pin "2") (pinfunction "2_2") (pintype "passive"))
      (node (ref "R41") (pin "2") (pinfunction "2_2") (pintype "passive"))
      (node (ref "R42") (pin "2") (pinfunction "2_2") (pintype "passive"))
      (node (ref "R43") (pin "2") (pinfunction "2_2") (pintype "passive"))
      (node (ref "SD1") (pin "4") (pinfunction "4_4") (pintype "bidirectional"))
      (node (ref "T2") (pin "1") (pinfunction "D_1") (pintype "passive"))
    )
    (net (code "141") (name "TXD_HOST") (class "Default")
      (node (ref "J1") (pin "P$2") (pinfunction "2-LEFT_P$2") (pintype "bidirectional"))
      (node (ref "R25") (pin "2") (pinfunction "2_2") (pintype "passive"))
    )
    (net (code "142") (name "UA1") (class "Default")
      (node (ref "C50") (pin "1") (pinfunction "1_1") (pintype "passive"))
      (node (ref "C52") (pin "1") (pinfunction "1_1") (pintype "passive"))
      (node (ref "C54") (pin "1") (pinfunction "1_1") (pintype "passive"))
      (node (ref "F2") (pin "P$1") (pinfunction "1_P$1") (pintype "passive"))
      (node (ref "L3") (pin "2") (pinfunction "2_2") (pintype "passive"))
      (node (ref "LSP1") (pin "MP") (pinfunction "MP_MP") (pintype "passive"))
      (node (ref "R56") (pin "2") (pinfunction "2_2") (pintype "passive"))
      (node (ref "R62") (pin "2") (pinfunction "2_2") (pintype "passive"))
      (node (ref "R74") (pin "2") (pinfunction "2_2") (pintype "passive"))
      (node (ref "R77") (pin "2") (pinfunction "2_2") (pintype "passive"))
    )
    (net (code "143") (name "UA1_OUT") (class "Default")
      (node (ref "F2") (pin "P$2") (pinfunction "2_P$2") (pintype "passive"))
      (node (ref "X2") (pin "5") (pinfunction "1_5") (pintype "passive"))
    )
    (net (code "144") (name "UA2") (class "Default")
      (node (ref "C51") (pin "1") (pinfunction "1_1") (pintype "passive"))
      (node (ref "C53") (pin "1") (pinfunction "1_1") (pintype "passive"))
      (node (ref "C55") (pin "1") (pinfunction "1_1") (pintype "passive"))
      (node (ref "F3") (pin "P$1") (pinfunction "1_P$1") (pintype "passive"))
      (node (ref "L4") (pin "2") (pinfunction "2_2") (pintype "passive"))
      (node (ref "LSP2") (pin "MP") (pinfunction "MP_MP") (pintype "passive"))
      (node (ref "R59") (pin "2") (pinfunction "2_2") (pintype "passive"))
      (node (ref "R63") (pin "2") (pinfunction "2_2") (pintype "passive"))
      (node (ref "R81") (pin "2") (pinfunction "2_2") (pintype "passive"))
      (node (ref "R83") (pin "2") (pinfunction "2_2") (pintype "passive"))
    )
    (net (code "145") (name "UA2_OUT") (class "Default")
      (node (ref "F3") (pin "P$2") (pinfunction "2_P$2") (pintype "passive"))
      (node (ref "X2") (pin "7") (pinfunction "1_7") (pintype "passive"))
    )
    (net (code "146") (name "VDCF") (class "Default")
      (node (ref "C6") (pin "+") (pinfunction "+_+") (pintype "passive"))
      (node (ref "C7") (pin "1") (pinfunction "1_1") (pintype "passive"))
      (node (ref "D1") (pin "1") (pinfunction "C_1") (pintype "passive"))
      (node (ref "X4") (pin "4") (pinfunction "1_4") (pintype "passive"))
    )
    (net (code "147") (name "VMCU") (class "Default")
      (node (ref "C14") (pin "2") (pinfunction "2_2") (pintype "passive"))
      (node (ref "C15") (pin "2") (pinfunction "2_2") (pintype "passive"))
      (node (ref "C16") (pin "2") (pinfunction "2_2") (pintype "passive"))
      (node (ref "C20") (pin "2") (pinfunction "2_2") (pintype "passive"))
      (node (ref "C22") (pin "2") (pinfunction "2_2") (pintype "passive"))
      (node (ref "C24") (pin "2") (pinfunction "2_2") (pintype "passive"))
      (node (ref "C25") (pin "2") (pinfunction "2_2") (pintype "passive"))
      (node (ref "C9") (pin "2") (pinfunction "2_2") (pintype "passive"))
      (node (ref "D3") (pin "1") (pinfunction "C_1") (pintype "passive"))
      (node (ref "IC2") (pin "26") (pinfunction "IOVDD_3_26") (pintype "power_in"))
      (node (ref "IC2") (pin "39") (pinfunction "VDD_DREG_39") (pintype "power_in"))
      (node (ref "IC2") (pin "55") (pinfunction "IOVDD_5_55") (pintype "power_in"))
      (node (ref "IC2") (pin "8") (pinfunction "IOVDD_0_8") (pintype "power_in"))
      (node (ref "L2") (pin "1") (pinfunction "1_1") (pintype "passive"))
      (node (ref "R13") (pin "1") (pinfunction "1_1") (pintype "passive"))
      (node (ref "R15") (pin "2") (pinfunction "2_2") (pintype "passive"))
      (node (ref "R16") (pin "2") (pinfunction "2_2") (pintype "passive"))
      (node (ref "R17") (pin "2") (pinfunction "2_2") (pintype "passive"))
      (node (ref "R18") (pin "2") (pinfunction "2_2") (pintype "passive"))
      (node (ref "R19") (pin "2") (pinfunction "2_2") (pintype "passive"))
      (node (ref "R2") (pin "1") (pinfunction "1_1") (pintype "passive"))
      (node (ref "R20") (pin "2") (pinfunction "2_2") (pintype "passive"))
      (node (ref "R21") (pin "2") (pinfunction "2_2") (pintype "passive"))
      (node (ref "R22") (pin "2") (pinfunction "2_2") (pintype "passive"))
      (node (ref "R23") (pin "2") (pinfunction "2_2") (pintype "passive"))
      (node (ref "R24") (pin "2") (pinfunction "2_2") (pintype "passive"))
      (node (ref "R27") (pin "2") (pinfunction "2_2") (pintype "passive"))
      (node (ref "R3") (pin "1") (pinfunction "1_1") (pintype "passive"))
      (node (ref "R6") (pin "2") (pinfunction "2_2") (pintype "passive"))
      (node (ref "R88") (pin "2") (pinfunction "2_2") (pintype "passive"))
      (node (ref "T10") (pin "2") (pinfunction "S_2") (pintype "passive"))
      (node (ref "X5") (pin "1") (pinfunction "1_1") (pintype "passive"))
    )
    (net (code "148") (name "VSD") (class "Default")
      (node (ref "C5") (pin "+") (pinfunction "+_+") (pintype "passive"))
      (node (ref "C8") (pin "1") (pinfunction "1_1") (pintype "passive"))
      (node (ref "D2") (pin "1") (pinfunction "C_1") (pintype "passive"))
      (node (ref "R35") (pin "2") (pinfunction "2_2") (pintype "passive"))
      (node (ref "T2") (pin "2") (pinfunction "S_2") (pintype "passive"))
    )
    (net (code "149") (name "unconnected-(IC2C-PC11{slash}ACMP1_CH3{slash}US0_TX#2-Pad44)") (class "Default")
      (node (ref "IC2") (pin "44") (pinfunction "PC11/ACMP1_CH3/US0_TX#2_44") (pintype "bidirectional"))
    )
    (net (code "150") (name "unconnected-(IC3-PWGD-Pad6)") (class "Default")
      (node (ref "IC3") (pin "6") (pinfunction "PWGD_6") (pintype "output"))
    )
    (net (code "151") (name "unconnected-(IC4-PWGD-Pad6)") (class "Default")
      (node (ref "IC4") (pin "6") (pinfunction "PWGD_6") (pintype "output"))
    )
    (net (code "152") (name "unconnected-(SD1-PadG1)") (class "Default")
      (node (ref "SD1") (pin "G1") (pinfunction "G1_G1") (pintype "passive"))
    )
    (net (code "153") (name "unconnected-(SD1-PadG2)") (class "Default")
      (node (ref "SD1") (pin "G2") (pinfunction "G2_G2") (pintype "passive"))
    )
    (net (code "154") (name "unconnected-(SD1-PadG3)") (class "Default")
      (node (ref "SD1") (pin "G3") (pinfunction "G3_G3") (pintype "passive"))
    )
    (net (code "155") (name "unconnected-(SD1-PadG4)") (class "Default")
      (node (ref "SD1") (pin "G4") (pinfunction "G4_G4") (pintype "passive"))
    )
    (net (code "156") (name "unconnected-(X5-Pad7)") (class "Default")
      (node (ref "X5") (pin "7") (pinfunction "7_7") (pintype "passive"))
    )
  )
)
